# Termo3.net
KiCad netlist of a schematic drawn in EAGLE
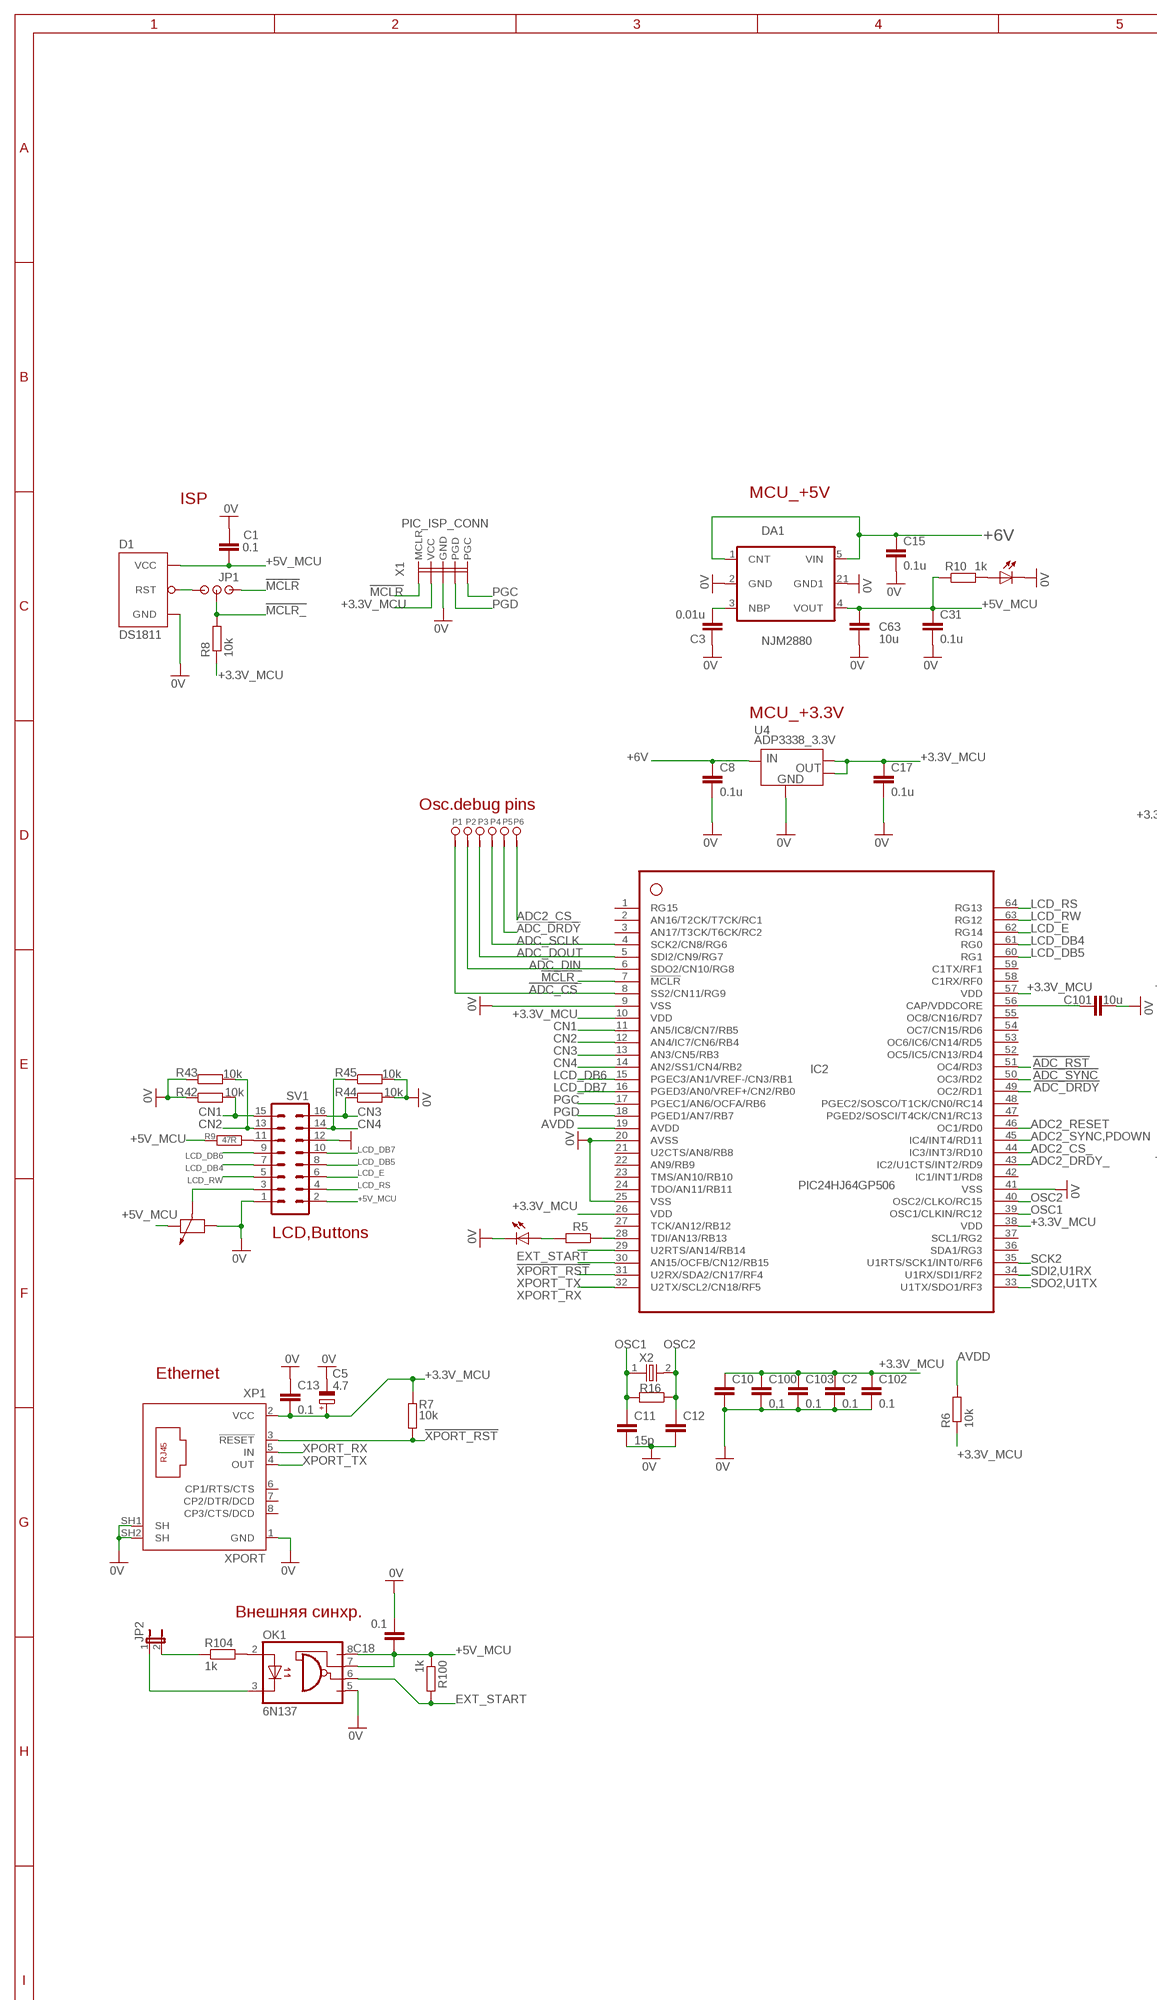
[diagram p0: schematic, sheet 1, part 1 of 2]
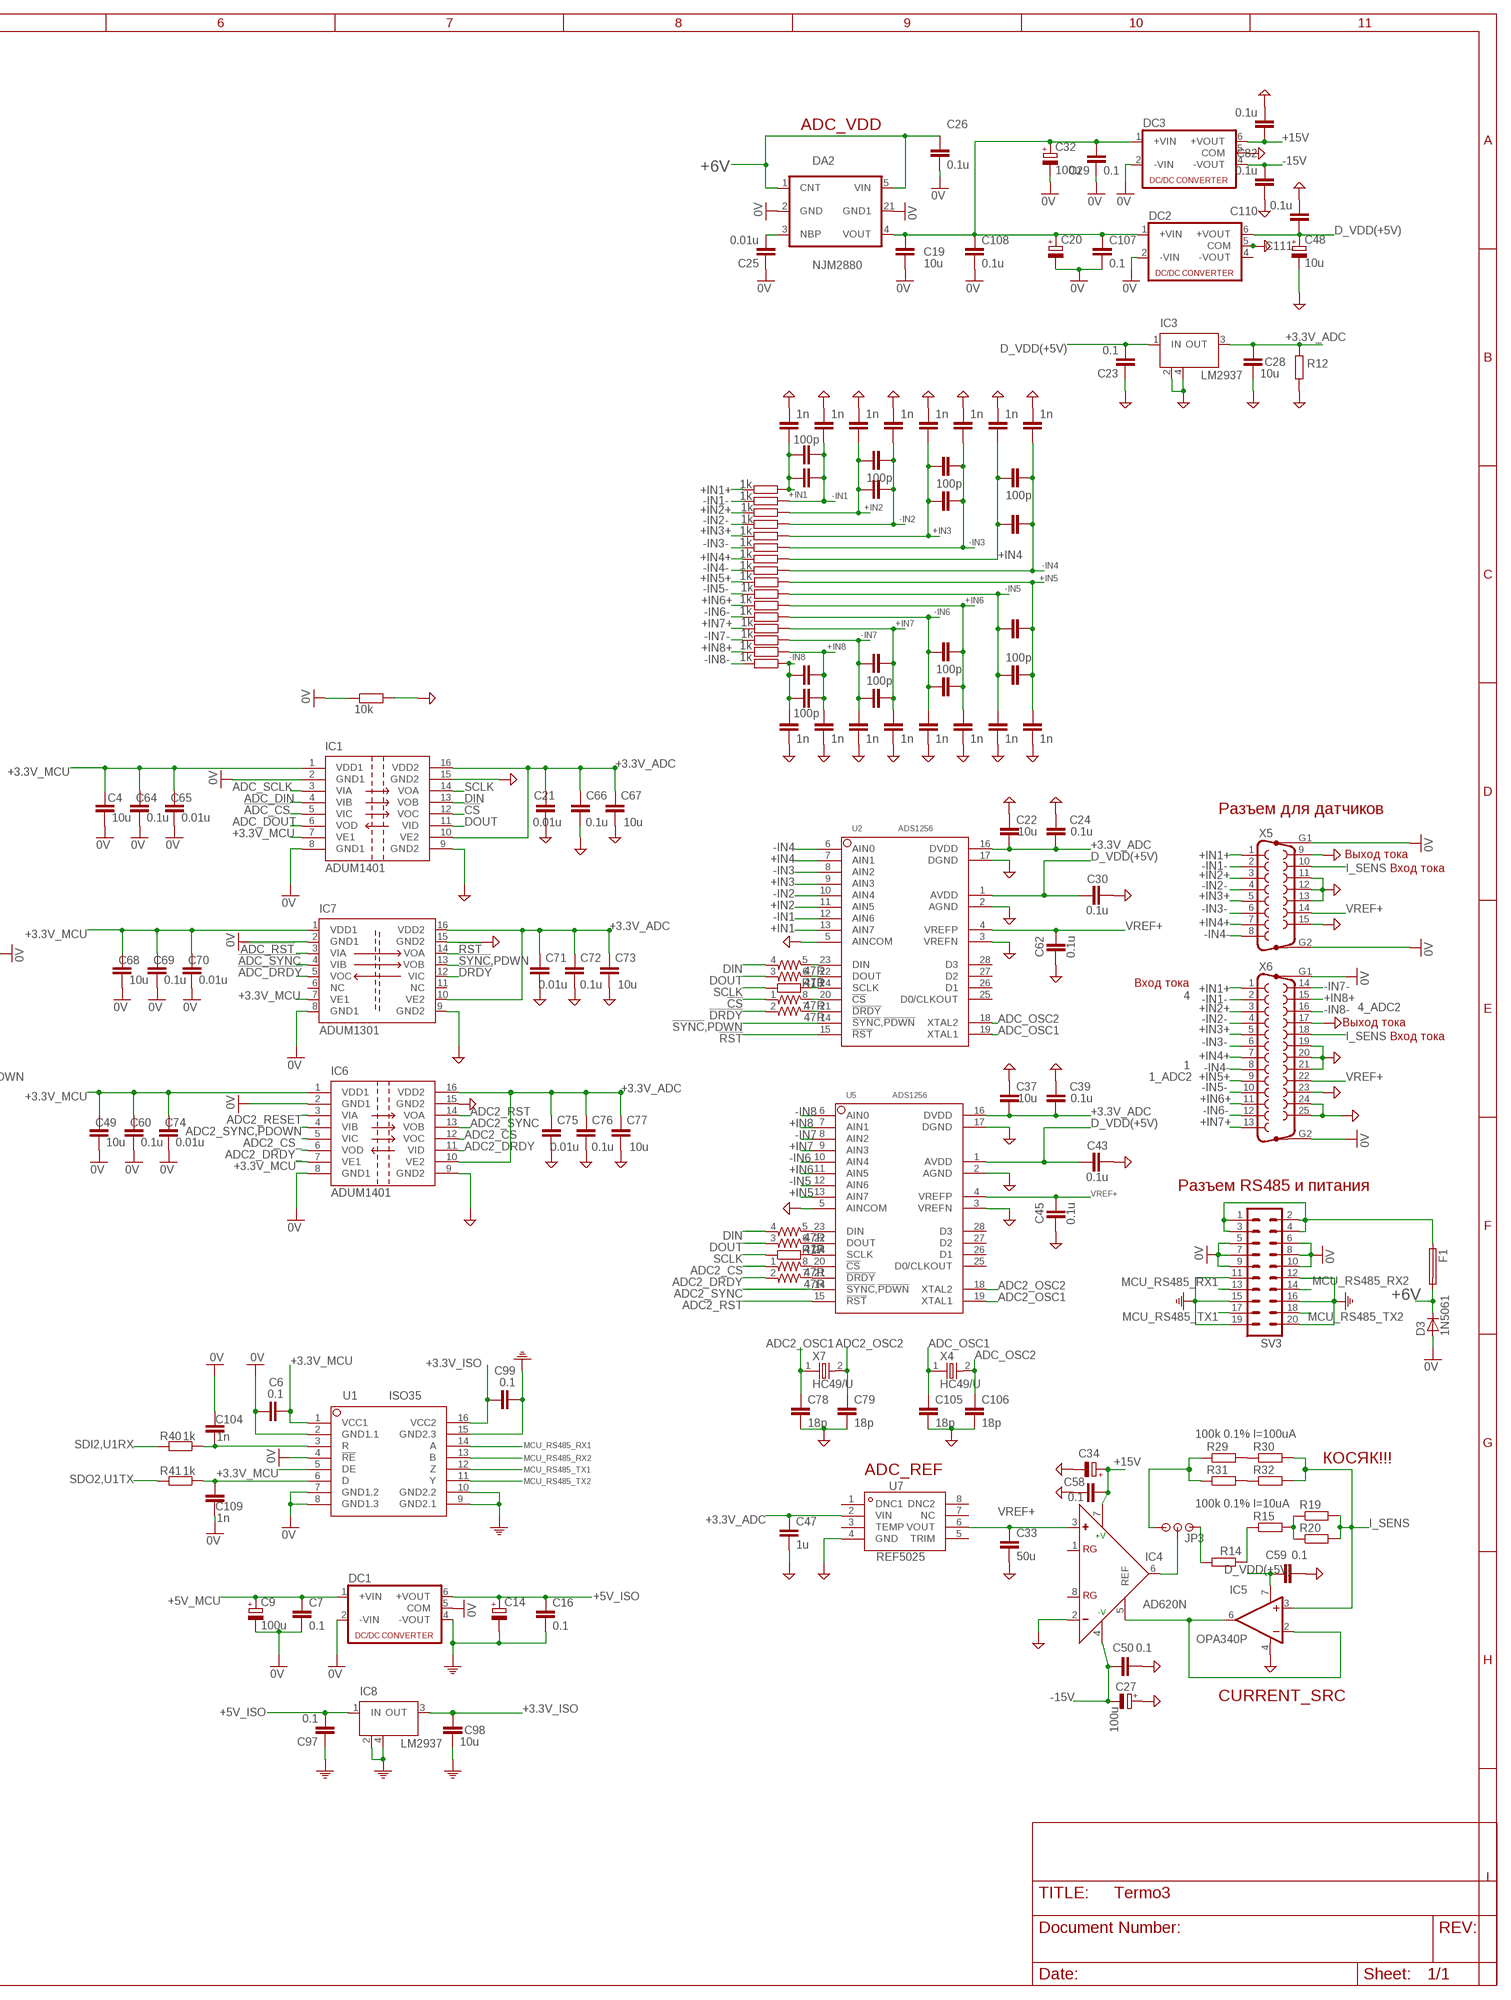
[diagram p1: schematic, sheet 1, part 2 of 2]

(export (version "E")
  (design (tool "Eeschema 10.0.6"))
  (components
    (comp (ref "C1")
      (value "0.1")
      (footprint "eagle-import:C0805D")
      (libsource (lib "eagle-import") (part "C0805"))
    )
    (comp (ref "C2")
      (value "0.1")
      (footprint "eagle-import:C0805D")
      (libsource (lib "eagle-import") (part "C0805"))
    )
    (comp (ref "C3")
      (value "0.01u")
      (footprint "eagle-import:C0805D")
      (libsource (lib "eagle-import") (part "C0805"))
    )
    (comp (ref "C4")
      (value "10u")
      (footprint "eagle-import:C0805D")
      (libsource (lib "eagle-import") (part "C0805"))
    )
    (comp (ref "C5")
      (value "4.7")
      (footprint "eagle-import:C100MILX6X12")
      (libsource (lib "eagle-import") (part "C100MFX25V"))
    )
    (comp (ref "C6")
      (value "0.1")
      (footprint "eagle-import:C0805D")
      (libsource (lib "eagle-import") (part "C0805"))
    )
    (comp (ref "C7")
      (value "0.1")
      (footprint "eagle-import:C0805D")
      (libsource (lib "eagle-import") (part "C0805"))
    )
    (comp (ref "C8")
      (value "0.1u")
      (footprint "eagle-import:C0805D")
      (libsource (lib "eagle-import") (part "C0805"))
    )
    (comp (ref "C9")
      (value "100u")
      (footprint "eagle-import:C100MILX6X12")
      (libsource (lib "eagle-import") (part "C100MFX25V"))
    )
    (comp (ref "C10")
      (value "C0805")
      (footprint "eagle-import:C0805D")
      (libsource (lib "eagle-import") (part "C0805"))
    )
    (comp (ref "C11")
      (value "15p")
      (footprint "eagle-import:C0805D")
      (libsource (lib "eagle-import") (part "C0805"))
    )
    (comp (ref "C12")
      (value "C0805")
      (footprint "eagle-import:C0805D")
      (libsource (lib "eagle-import") (part "C0805"))
    )
    (comp (ref "C13")
      (value "0.1")
      (footprint "eagle-import:C0805D")
      (libsource (lib "eagle-import") (part "C0805"))
    )
    (comp (ref "C14")
      (value "C100MFX25V")
      (footprint "eagle-import:C100MILX6X12")
      (libsource (lib "eagle-import") (part "C100MFX25V"))
    )
    (comp (ref "C15")
      (value "0.1u")
      (footprint "eagle-import:C0805D")
      (libsource (lib "eagle-import") (part "C0805"))
    )
    (comp (ref "C16")
      (value "0.1")
      (footprint "eagle-import:C0805D")
      (libsource (lib "eagle-import") (part "C0805"))
    )
    (comp (ref "C17")
      (value "0.1u")
      (footprint "eagle-import:C0805D")
      (libsource (lib "eagle-import") (part "C0805"))
    )
    (comp (ref "C18")
      (value "0.1")
      (footprint "eagle-import:C0805D")
      (libsource (lib "eagle-import") (part "C0805"))
    )
    (comp (ref "C19")
      (value "10u")
      (footprint "eagle-import:C0805D")
      (libsource (lib "eagle-import") (part "C0805"))
    )
    (comp (ref "C20")
      (value "C100MFX25V")
      (footprint "eagle-import:C100MILX6X12")
      (libsource (lib "eagle-import") (part "C100MFX25V"))
    )
    (comp (ref "C21")
      (value "0.01u")
      (footprint "eagle-import:C0805D")
      (libsource (lib "eagle-import") (part "C0805"))
    )
    (comp (ref "C22")
      (value "10u")
      (footprint "eagle-import:C0805D")
      (libsource (lib "eagle-import") (part "C0805"))
    )
    (comp (ref "C23")
      (value "0.1")
      (footprint "eagle-import:C0805D")
      (libsource (lib "eagle-import") (part "C0805"))
    )
    (comp (ref "C24")
      (value "0.1u")
      (footprint "eagle-import:C0805D")
      (libsource (lib "eagle-import") (part "C0805"))
    )
    (comp (ref "C25")
      (value "0.01u")
      (footprint "eagle-import:C0805D")
      (libsource (lib "eagle-import") (part "C0805"))
    )
    (comp (ref "C26")
      (value "0.1u")
      (footprint "eagle-import:C0805D")
      (libsource (lib "eagle-import") (part "C0805"))
    )
    (comp (ref "C27")
      (value "100u")
      (footprint "eagle-import:C100MILX6X12")
      (libsource (lib "eagle-import") (part "C100MFX25V"))
    )
    (comp (ref "C28")
      (value "10u")
      (footprint "eagle-import:C0805D")
      (libsource (lib "eagle-import") (part "C0805"))
    )
    (comp (ref "C29")
      (value "0.1")
      (footprint "eagle-import:C0805D")
      (libsource (lib "eagle-import") (part "C0805"))
    )
    (comp (ref "C30")
      (value "0.1u")
      (footprint "eagle-import:C0805D")
      (libsource (lib "eagle-import") (part "C0805"))
    )
    (comp (ref "C31")
      (value "0.1u")
      (footprint "eagle-import:C0805D")
      (libsource (lib "eagle-import") (part "C0805"))
    )
    (comp (ref "C32")
      (value "100u")
      (footprint "eagle-import:C100MILX6X12")
      (libsource (lib "eagle-import") (part "C100MFX25V"))
    )
    (comp (ref "C33")
      (value "50u")
      (footprint "eagle-import:C0805D")
      (libsource (lib "eagle-import") (part "C0805"))
    )
    (comp (ref "C34")
      (value "C100MFX25V")
      (footprint "eagle-import:C100MILX6X12")
      (libsource (lib "eagle-import") (part "C100MFX25V"))
    )
    (comp (ref "C35")
      (value "100p")
      (footprint "eagle-import:C0805D")
      (libsource (lib "eagle-import") (part "C0805"))
    )
    (comp (ref "C36")
      (value "100p")
      (footprint "eagle-import:C0805D")
      (libsource (lib "eagle-import") (part "C0805"))
    )
    (comp (ref "C37")
      (value "10u")
      (footprint "eagle-import:C0805D")
      (libsource (lib "eagle-import") (part "C0805"))
    )
    (comp (ref "C38")
      (value "100p")
      (footprint "eagle-import:C0805D")
      (libsource (lib "eagle-import") (part "C0805"))
    )
    (comp (ref "C39")
      (value "0.1u")
      (footprint "eagle-import:C0805D")
      (libsource (lib "eagle-import") (part "C0805"))
    )
    (comp (ref "C40")
      (value "100p")
      (footprint "eagle-import:C0805D")
      (libsource (lib "eagle-import") (part "C0805"))
    )
    (comp (ref "C41")
      (value "1n")
      (footprint "eagle-import:C0805D")
      (libsource (lib "eagle-import") (part "C0805"))
    )
    (comp (ref "C42")
      (value "1n")
      (footprint "eagle-import:C0805D")
      (libsource (lib "eagle-import") (part "C0805"))
    )
    (comp (ref "C43")
      (value "0.1u")
      (footprint "eagle-import:C0805D")
      (libsource (lib "eagle-import") (part "C0805"))
    )
    (comp (ref "C44")
      (value "1n")
      (footprint "eagle-import:C0805D")
      (libsource (lib "eagle-import") (part "C0805"))
    )
    (comp (ref "C45")
      (value "0.1u")
      (footprint "eagle-import:C0805D")
      (libsource (lib "eagle-import") (part "C0805"))
    )
    (comp (ref "C46")
      (value "1n")
      (footprint "eagle-import:C0805D")
      (libsource (lib "eagle-import") (part "C0805"))
    )
    (comp (ref "C47")
      (value "1u")
      (footprint "eagle-import:C0805D")
      (libsource (lib "eagle-import") (part "C0805"))
    )
    (comp (ref "C48")
      (value "10u")
      (footprint "eagle-import:C100MILX6X12")
      (libsource (lib "eagle-import") (part "C100MFX25V"))
    )
    (comp (ref "C49")
      (value "10u")
      (footprint "eagle-import:C0805D")
      (libsource (lib "eagle-import") (part "C0805"))
    )
    (comp (ref "C50")
      (value "0.1")
      (footprint "eagle-import:C0805D")
      (libsource (lib "eagle-import") (part "C0805"))
    )
    (comp (ref "C51")
      (value "1n")
      (footprint "eagle-import:C0805D")
      (libsource (lib "eagle-import") (part "C0805"))
    )
    (comp (ref "C52")
      (value "1n")
      (footprint "eagle-import:C0805D")
      (libsource (lib "eagle-import") (part "C0805"))
    )
    (comp (ref "C53")
      (value "1n")
      (footprint "eagle-import:C0805D")
      (libsource (lib "eagle-import") (part "C0805"))
    )
    (comp (ref "C54")
      (value "1n")
      (footprint "eagle-import:C0805D")
      (libsource (lib "eagle-import") (part "C0805"))
    )
    (comp (ref "C55")
      (value "1n")
      (footprint "eagle-import:C0805D")
      (libsource (lib "eagle-import") (part "C0805"))
    )
    (comp (ref "C56")
      (value "1n")
      (footprint "eagle-import:C0805D")
      (libsource (lib "eagle-import") (part "C0805"))
    )
    (comp (ref "C57")
      (value "1n")
      (footprint "eagle-import:C0805D")
      (libsource (lib "eagle-import") (part "C0805"))
    )
    (comp (ref "C58")
      (value "0.1")
      (footprint "eagle-import:C0805D")
      (libsource (lib "eagle-import") (part "C0805"))
    )
    (comp (ref "C59")
      (value "0.1")
      (footprint "eagle-import:C0805D")
      (libsource (lib "eagle-import") (part "C0805"))
    )
    (comp (ref "C60")
      (value "0.1u")
      (footprint "eagle-import:C0805D")
      (libsource (lib "eagle-import") (part "C0805"))
    )
    (comp (ref "C61")
      (value "1n")
      (footprint "eagle-import:C0805D")
      (libsource (lib "eagle-import") (part "C0805"))
    )
    (comp (ref "C62")
      (value "0.1u")
      (footprint "eagle-import:C0805D")
      (libsource (lib "eagle-import") (part "C0805"))
    )
    (comp (ref "C63")
      (value "10u")
      (footprint "eagle-import:C0805D")
      (libsource (lib "eagle-import") (part "C0805"))
    )
    (comp (ref "C64")
      (value "0.1u")
      (footprint "eagle-import:C0805D")
      (libsource (lib "eagle-import") (part "C0805"))
    )
    (comp (ref "C65")
      (value "0.01u")
      (footprint "eagle-import:C0805D")
      (libsource (lib "eagle-import") (part "C0805"))
    )
    (comp (ref "C66")
      (value "0.1u")
      (footprint "eagle-import:C0805D")
      (libsource (lib "eagle-import") (part "C0805"))
    )
    (comp (ref "C67")
      (value "10u")
      (footprint "eagle-import:C0805D")
      (libsource (lib "eagle-import") (part "C0805"))
    )
    (comp (ref "C68")
      (value "10u")
      (footprint "eagle-import:C0805D")
      (libsource (lib "eagle-import") (part "C0805"))
    )
    (comp (ref "C69")
      (value "0.1u")
      (footprint "eagle-import:C0805D")
      (libsource (lib "eagle-import") (part "C0805"))
    )
    (comp (ref "C70")
      (value "0.01u")
      (footprint "eagle-import:C0805D")
      (libsource (lib "eagle-import") (part "C0805"))
    )
    (comp (ref "C71")
      (value "0.01u")
      (footprint "eagle-import:C0805D")
      (libsource (lib "eagle-import") (part "C0805"))
    )
    (comp (ref "C72")
      (value "0.1u")
      (footprint "eagle-import:C0805D")
      (libsource (lib "eagle-import") (part "C0805"))
    )
    (comp (ref "C73")
      (value "10u")
      (footprint "eagle-import:C0805D")
      (libsource (lib "eagle-import") (part "C0805"))
    )
    (comp (ref "C74")
      (value "0.01u")
      (footprint "eagle-import:C0805D")
      (libsource (lib "eagle-import") (part "C0805"))
    )
    (comp (ref "C75")
      (value "0.01u")
      (footprint "eagle-import:C0805D")
      (libsource (lib "eagle-import") (part "C0805"))
    )
    (comp (ref "C76")
      (value "0.1u")
      (footprint "eagle-import:C0805D")
      (libsource (lib "eagle-import") (part "C0805"))
    )
    (comp (ref "C77")
      (value "10u")
      (footprint "eagle-import:C0805D")
      (libsource (lib "eagle-import") (part "C0805"))
    )
    (comp (ref "C78")
      (value "18p")
      (footprint "eagle-import:C0805D")
      (libsource (lib "eagle-import") (part "C0805"))
    )
    (comp (ref "C79")
      (value "18p")
      (footprint "eagle-import:C0805D")
      (libsource (lib "eagle-import") (part "C0805"))
    )
    (comp (ref "C80")
      (value "1n")
      (footprint "eagle-import:C0805D")
      (libsource (lib "eagle-import") (part "C0805"))
    )
    (comp (ref "C81")
      (value "1n")
      (footprint "eagle-import:C0805D")
      (libsource (lib "eagle-import") (part "C0805"))
    )
    (comp (ref "C82")
      (value "0.1u")
      (footprint "eagle-import:C0805D")
      (libsource (lib "eagle-import") (part "C0805"))
    )
    (comp (ref "C83")
      (value "1n")
      (footprint "eagle-import:C0805D")
      (libsource (lib "eagle-import") (part "C0805"))
    )
    (comp (ref "C84")
      (value "1n")
      (footprint "eagle-import:C0805D")
      (libsource (lib "eagle-import") (part "C0805"))
    )
    (comp (ref "C85")
      (value "1n")
      (footprint "eagle-import:C0805D")
      (libsource (lib "eagle-import") (part "C0805"))
    )
    (comp (ref "C86")
      (value "1n")
      (footprint "eagle-import:C0805D")
      (libsource (lib "eagle-import") (part "C0805"))
    )
    (comp (ref "C87")
      (value "1n")
      (footprint "eagle-import:C0805D")
      (libsource (lib "eagle-import") (part "C0805"))
    )
    (comp (ref "C88")
      (value "1n")
      (footprint "eagle-import:C0805D")
      (libsource (lib "eagle-import") (part "C0805"))
    )
    (comp (ref "C89")
      (value "1n")
      (footprint "eagle-import:C0805D")
      (libsource (lib "eagle-import") (part "C0805"))
    )
    (comp (ref "C90")
      (value "100p")
      (footprint "eagle-import:C0805D")
      (libsource (lib "eagle-import") (part "C0805"))
    )
    (comp (ref "C91")
      (value "1n")
      (footprint "eagle-import:C0805D")
      (libsource (lib "eagle-import") (part "C0805"))
    )
    (comp (ref "C92")
      (value "1n")
      (footprint "eagle-import:C0805D")
      (libsource (lib "eagle-import") (part "C0805"))
    )
    (comp (ref "C93")
      (value "1n")
      (footprint "eagle-import:C0805D")
      (libsource (lib "eagle-import") (part "C0805"))
    )
    (comp (ref "C94")
      (value "100p")
      (footprint "eagle-import:C0805D")
      (libsource (lib "eagle-import") (part "C0805"))
    )
    (comp (ref "C95")
      (value "100p")
      (footprint "eagle-import:C0805D")
      (libsource (lib "eagle-import") (part "C0805"))
    )
    (comp (ref "C96")
      (value "100p")
      (footprint "eagle-import:C0805D")
      (libsource (lib "eagle-import") (part "C0805"))
    )
    (comp (ref "C97")
      (value "0.1")
      (footprint "eagle-import:C0805D")
      (libsource (lib "eagle-import") (part "C0805"))
    )
    (comp (ref "C98")
      (value "10u")
      (footprint "eagle-import:C0805D")
      (libsource (lib "eagle-import") (part "C0805"))
    )
    (comp (ref "C99")
      (value "0.1")
      (footprint "eagle-import:C0805D")
      (libsource (lib "eagle-import") (part "C0805"))
    )
    (comp (ref "C100")
      (value "0,1")
      (footprint "eagle-import:C0805D")
      (libsource (lib "eagle-import") (part "C0805"))
    )
    (comp (ref "C101")
      (value "10u")
      (footprint "eagle-import:C0805D")
      (libsource (lib "eagle-import") (part "C0805"))
    )
    (comp (ref "C102")
      (value "0.1")
      (footprint "eagle-import:C0805D")
      (libsource (lib "eagle-import") (part "C0805"))
    )
    (comp (ref "C103")
      (value "0.1")
      (footprint "eagle-import:C0805D")
      (libsource (lib "eagle-import") (part "C0805"))
    )
    (comp (ref "C104")
      (value "1n")
      (footprint "eagle-import:C0805D")
      (libsource (lib "eagle-import") (part "C0805"))
    )
    (comp (ref "C105")
      (value "18p")
      (footprint "eagle-import:C0805D")
      (libsource (lib "eagle-import") (part "C0805"))
    )
    (comp (ref "C106")
      (value "18p")
      (footprint "eagle-import:C0805D")
      (libsource (lib "eagle-import") (part "C0805"))
    )
    (comp (ref "C107")
      (value "0.1")
      (footprint "eagle-import:C0805D")
      (libsource (lib "eagle-import") (part "C0805"))
    )
    (comp (ref "C108")
      (value "0.1u")
      (footprint "eagle-import:C0805D")
      (libsource (lib "eagle-import") (part "C0805"))
    )
    (comp (ref "C109")
      (value "1n")
      (footprint "eagle-import:C0805D")
      (libsource (lib "eagle-import") (part "C0805"))
    )
    (comp (ref "C110")
      (value "0.1u")
      (footprint "eagle-import:C0805D")
      (libsource (lib "eagle-import") (part "C0805"))
    )
    (comp (ref "C111")
      (value "0.1u")
      (footprint "eagle-import:C0805D")
      (libsource (lib "eagle-import") (part "C0805"))
    )
    (comp (ref "D1")
      (value "DS1811")
      (footprint "eagle-import:TO92-60")
      (libsource (lib "eagle-import") (part "DS1811"))
    )
    (comp (ref "D3")
      (value "1N5061")
      (footprint "eagle-import:DO41-10")
      (libsource (lib "eagle-import") (part "1N5061"))
    )
    (comp (ref "DA1")
      (value "NJM2880")
      (footprint "eagle-import:SOT89-5")
      (libsource (lib "eagle-import") (part "NJM2880"))
    )
    (comp (ref "DA2")
      (value "NJM2880")
      (footprint "eagle-import:SOT89-5")
      (libsource (lib "eagle-import") (part "NJM2880"))
    )
    (comp (ref "DC1")
      (value "NMA")
      (footprint "eagle-import:NMA")
      (fields (field (name "MF") "C & D TECHNOLOGIES, INC") (field (name "MPN") "NMA0515SC"))
      (libsource (lib "eagle-import") (part "NMA"))
    )
    (comp (ref "DC2")
      (value "NMA")
      (footprint "eagle-import:NMA")
      (fields (field (name "MF") "C & D TECHNOLOGIES, INC") (field (name "MPN") "NMA0515SC"))
      (libsource (lib "eagle-import") (part "NMA"))
    )
    (comp (ref "DC3")
      (value "NMA")
      (footprint "eagle-import:NMA")
      (fields (field (name "MF") "C & D TECHNOLOGIES, INC") (field (name "MPN") "NMA0515SC"))
      (libsource (lib "eagle-import") (part "NMA"))
    )
    (comp (ref "F1")
      (value "TE5")
      (footprint "eagle-import:TE5")
      (libsource (lib "eagle-import") (part "TE5"))
    )
    (comp (ref "HL2")
      (value "LED3MM")
      (footprint "eagle-import:LED3MM")
      (libsource (lib "eagle-import") (part "LED3MM"))
    )
    (comp (ref "HL6")
      (value "LED3MM")
      (footprint "eagle-import:LED3MM")
      (libsource (lib "eagle-import") (part "LED3MM"))
    )
    (comp (ref "IC1")
      (value "ADUM1401")
      (footprint "eagle-import:SO16W")
      (libsource (lib "eagle-import") (part "ADUM1401"))
    )
    (comp (ref "IC2")
      (value "PIC24HJ64GP506")
      (footprint "eagle-import:TQFP64-10X10")
      (fields (field (name "MPN") "PIC24HJ64GP506A-I/PT"))
      (libsource (lib "eagle-import") (part "PIC24HJ64GP506"))
    )
    (comp (ref "IC3")
      (value "LM2937")
      (footprint "eagle-import:SOT223")
      (libsource (lib "eagle-import") (part "LM2937"))
    )
    (comp (ref "IC4")
      (value "AD620N")
      (footprint "eagle-import:DIL08")
      (fields (field (name "MF") "ALTERA CORPORATION") (field (name "MPN") "AD620AN"))
      (libsource (lib "eagle-import") (part "AD620N"))
    )
    (comp (ref "IC5")
      (value "OPA340P")
      (footprint "eagle-import:DIL08")
      (fields (field (name "MPN") "OPA340PA"))
      (libsource (lib "eagle-import") (part "OPA340P"))
    )
    (comp (ref "IC6")
      (value "ADUM1401")
      (footprint "eagle-import:SO16W")
      (libsource (lib "eagle-import") (part "ADUM1401"))
    )
    (comp (ref "IC7")
      (value "ADUM1301")
      (footprint "eagle-import:SO-16W")
      (fields (field (name "MPN") "ADUM1301BRWZ"))
      (libsource (lib "eagle-import") (part "ADUM1301"))
    )
    (comp (ref "IC8")
      (value "LM2937")
      (footprint "eagle-import:SOT223")
      (libsource (lib "eagle-import") (part "LM2937"))
    )
    (comp (ref "JP1")
      (value "JP3PIN")
      (footprint "eagle-import:PLC-3PIN")
      (libsource (lib "eagle-import") (part "JP3PIN"))
    )
    (comp (ref "JP2")
      (value "JP1E")
      (footprint "eagle-import:JP1")
      (libsource (lib "eagle-import") (part "JP1E"))
    )
    (comp (ref "JP3")
      (value "JP3PIN")
      (footprint "eagle-import:PLC-3PIN")
      (libsource (lib "eagle-import") (part "JP3PIN"))
    )
    (comp (ref "OK1")
      (value "6N137")
      (footprint "eagle-import:DIL08")
      (libsource (lib "eagle-import") (part "6N137"))
    )
    (comp (ref "P1")
      (value "1_PIN_CON")
      (footprint "eagle-import:1_PIN_CON")
      (libsource (lib "eagle-import") (part "1_PIN_CON"))
    )
    (comp (ref "P2")
      (value "1_PIN_CON")
      (footprint "eagle-import:1_PIN_CON")
      (libsource (lib "eagle-import") (part "1_PIN_CON"))
    )
    (comp (ref "P3")
      (value "1_PIN_CON")
      (footprint "eagle-import:1_PIN_CON")
      (libsource (lib "eagle-import") (part "1_PIN_CON"))
    )
    (comp (ref "P4")
      (value "1_PIN_CON")
      (footprint "eagle-import:1_PIN_CON")
      (libsource (lib "eagle-import") (part "1_PIN_CON"))
    )
    (comp (ref "P5")
      (value "1_PIN_CON")
      (footprint "eagle-import:1_PIN_CON")
      (libsource (lib "eagle-import") (part "1_PIN_CON"))
    )
    (comp (ref "P6")
      (value "1_PIN_CON")
      (footprint "eagle-import:1_PIN_CON")
      (libsource (lib "eagle-import") (part "1_PIN_CON"))
    )
    (comp (ref "POT1")
      (value "RTRIM3329H")
      (footprint "eagle-import:RTRIM3329H")
      (libsource (lib "eagle-import") (part "RTRIM3329H"))
    )
    (comp (ref "R5")
      (value "51R")
      (footprint "eagle-import:R0805D")
      (libsource (lib "eagle-import") (part "R0805"))
    )
    (comp (ref "R6")
      (value "10k")
      (footprint "eagle-import:R0805D")
      (libsource (lib "eagle-import") (part "R0805"))
    )
    (comp (ref "R7")
      (value "10k")
      (footprint "eagle-import:R0805D")
      (libsource (lib "eagle-import") (part "R0805"))
    )
    (comp (ref "R8")
      (value "10k")
      (footprint "eagle-import:R0805D")
      (libsource (lib "eagle-import") (part "R0805"))
    )
    (comp (ref "R9")
      (value "47R")
      (footprint "eagle-import:0207_10")
      (libsource (lib "eagle-import") (part "MLT025{dblquote}"))
    )
    (comp (ref "R10")
      (value "1k")
      (footprint "eagle-import:R0805D")
      (libsource (lib "eagle-import") (part "R0805"))
    )
    (comp (ref "R11")
      (value "10k")
      (footprint "eagle-import:R0805D")
      (libsource (lib "eagle-import") (part "R0805"))
    )
    (comp (ref "R12")
      (value "1k")
      (footprint "eagle-import:R0805D")
      (libsource (lib "eagle-import") (part "R0805"))
    )
    (comp (ref "R13")
      (value "51R")
      (footprint "eagle-import:R0805D")
      (libsource (lib "eagle-import") (part "R0805"))
    )
    (comp (ref "R14")
      (value "MLT025\"")
      (footprint "eagle-import:0207_10")
      (libsource (lib "eagle-import") (part "MLT025{dblquote}"))
    )
    (comp (ref "R15")
      (value "100k 0.1% I=10uA")
      (footprint "eagle-import:0207_10")
      (libsource (lib "eagle-import") (part "MLT025{dblquote}"))
    )
    (comp (ref "R16")
      (value "1M")
      (footprint "eagle-import:R0805D")
      (libsource (lib "eagle-import") (part "R0805"))
    )
    (comp (ref "R17")
      (value "51R")
      (footprint "eagle-import:R0805D")
      (libsource (lib "eagle-import") (part "R0805"))
    )
    (comp (ref "R18")
      (value "1k")
      (footprint "eagle-import:R0805D")
      (libsource (lib "eagle-import") (part "R0805"))
    )
    (comp (ref "R19")
      (value "MLT025\"")
      (footprint "eagle-import:0207_10")
      (libsource (lib "eagle-import") (part "MLT025{dblquote}"))
    )
    (comp (ref "R20")
      (value "MLT025\"")
      (footprint "eagle-import:0207_10")
      (libsource (lib "eagle-import") (part "MLT025{dblquote}"))
    )
    (comp (ref "R21")
      (value "1k")
      (footprint "eagle-import:R0805D")
      (libsource (lib "eagle-import") (part "R0805"))
    )
    (comp (ref "R22")
      (value "1k")
      (footprint "eagle-import:R0805D")
      (libsource (lib "eagle-import") (part "R0805"))
    )
    (comp (ref "R23")
      (value "1k")
      (footprint "eagle-import:R0805D")
      (libsource (lib "eagle-import") (part "R0805"))
    )
    (comp (ref "R24")
      (value "1k")
      (footprint "eagle-import:R0805D")
      (libsource (lib "eagle-import") (part "R0805"))
    )
    (comp (ref "R25")
      (value "1k")
      (footprint "eagle-import:R0805D")
      (libsource (lib "eagle-import") (part "R0805"))
    )
    (comp (ref "R26")
      (value "1k")
      (footprint "eagle-import:R0805D")
      (libsource (lib "eagle-import") (part "R0805"))
    )
    (comp (ref "R27")
      (value "1k")
      (footprint "eagle-import:R0805D")
      (libsource (lib "eagle-import") (part "R0805"))
    )
    (comp (ref "R28")
      (value "1k")
      (footprint "eagle-import:R0805D")
      (libsource (lib "eagle-import") (part "R0805"))
    )
    (comp (ref "R29")
      (value "100k 0.1% I=100uA")
      (footprint "eagle-import:0207_10")
      (libsource (lib "eagle-import") (part "MLT025{dblquote}"))
    )
    (comp (ref "R30")
      (value "MLT025\"")
      (footprint "eagle-import:0207_10")
      (libsource (lib "eagle-import") (part "MLT025{dblquote}"))
    )
    (comp (ref "R31")
      (value "MLT025\"")
      (footprint "eagle-import:0207_10")
      (libsource (lib "eagle-import") (part "MLT025{dblquote}"))
    )
    (comp (ref "R32")
      (value "MLT025\"")
      (footprint "eagle-import:0207_10")
      (libsource (lib "eagle-import") (part "MLT025{dblquote}"))
    )
    (comp (ref "R33")
      (value "1k")
      (footprint "eagle-import:R0805D")
      (libsource (lib "eagle-import") (part "R0805"))
    )
    (comp (ref "R34")
      (value "1k")
      (footprint "eagle-import:R0805D")
      (libsource (lib "eagle-import") (part "R0805"))
    )
    (comp (ref "R35")
      (value "1k")
      (footprint "eagle-import:R0805D")
      (libsource (lib "eagle-import") (part "R0805"))
    )
    (comp (ref "R36")
      (value "1k")
      (footprint "eagle-import:R0805D")
      (libsource (lib "eagle-import") (part "R0805"))
    )
    (comp (ref "R37")
      (value "1k")
      (footprint "eagle-import:R0805D")
      (libsource (lib "eagle-import") (part "R0805"))
    )
    (comp (ref "R38")
      (value "1k")
      (footprint "eagle-import:R0805D")
      (libsource (lib "eagle-import") (part "R0805"))
    )
    (comp (ref "R39")
      (value "1k")
      (footprint "eagle-import:R0805D")
      (libsource (lib "eagle-import") (part "R0805"))
    )
    (comp (ref "R40")
      (value "1k")
      (footprint "eagle-import:R0805D")
      (libsource (lib "eagle-import") (part "R0805"))
    )
    (comp (ref "R41")
      (value "1k")
      (footprint "eagle-import:R0805D")
      (libsource (lib "eagle-import") (part "R0805"))
    )
    (comp (ref "R42")
      (value "10k")
      (footprint "eagle-import:R0805D")
      (libsource (lib "eagle-import") (part "R0805"))
    )
    (comp (ref "R43")
      (value "10k")
      (footprint "eagle-import:R0805D")
      (libsource (lib "eagle-import") (part "R0805"))
    )
    (comp (ref "R44")
      (value "10k")
      (footprint "eagle-import:R0805D")
      (libsource (lib "eagle-import") (part "R0805"))
    )
    (comp (ref "R45")
      (value "10k")
      (footprint "eagle-import:R0805D")
      (libsource (lib "eagle-import") (part "R0805"))
    )
    (comp (ref "R100")
      (value "1k")
      (footprint "eagle-import:R0805D")
      (libsource (lib "eagle-import") (part "R0805"))
    )
    (comp (ref "R104")
      (value "1k")
      (footprint "eagle-import:R0805D")
      (libsource (lib "eagle-import") (part "R0805"))
    )
    (comp (ref "RN1")
      (value "47R")
      (footprint "eagle-import:742-8NS")
      (libsource (lib "eagle-import") (part "742-8_SNS"))
    )
    (comp (ref "RN2")
      (value "47R")
      (footprint "eagle-import:742-8NS")
      (libsource (lib "eagle-import") (part "742-8_SNS"))
    )
    (comp (ref "SV1")
      (value "ML16")
      (footprint "eagle-import:ML16")
      (fields (field (name "OC_FARNELL") "unknown") (field (name "OC_NEWARK") "unknown"))
      (libsource (lib "eagle-import") (part "ML16"))
    )
    (comp (ref "SV3")
      (value "ML20L")
      (footprint "eagle-import:ML20L")
      (libsource (lib "eagle-import") (part "ML20L"))
    )
    (comp (ref "U1")
      (value "ISO35")
      (footprint "eagle-import:ISO35_SOIC16")
      (libsource (lib "eagle-import") (part "ISO35"))
    )
    (comp (ref "U2")
      (value "ADS1256")
      (footprint "eagle-import:PCM2705-TSSOP28")
      (libsource (lib "eagle-import") (part "ADS1256"))
    )
    (comp (ref "U4")
      (value "ADP3338_3.3V")
      (footprint "eagle-import:SOT223")
      (libsource (lib "eagle-import") (part "ADP3338_3.3V"))
    )
    (comp (ref "U5")
      (value "ADS1256")
      (footprint "eagle-import:PCM2705-TSSOP28")
      (libsource (lib "eagle-import") (part "ADS1256"))
    )
    (comp (ref "U7")
      (value "REF5025")
      (footprint "eagle-import:SO08")
      (libsource (lib "eagle-import") (part "REF5025"))
    )
    (comp (ref "X1")
      (value "PIC_ISP_CONN")
      (footprint "eagle-import:PLC-5PIN")
      (libsource (lib "eagle-import") (part "PIC_ISP_CONN"))
    )
    (comp (ref "X2")
      (value "10MEG")
      (footprint "eagle-import:HC49U-V")
      (libsource (lib "eagle-import") (part "HC49/U"))
    )
    (comp (ref "X4")
      (value "HC49/U")
      (footprint "eagle-import:HC49U-V")
      (libsource (lib "eagle-import") (part "HC49/U"))
    )
    (comp (ref "X5")
      (value "F15HP")
      (footprint "eagle-import:F15HP")
      (libsource (lib "eagle-import") (part "F15HP"))
    )
    (comp (ref "X6")
      (value "F25HP")
      (footprint "eagle-import:F25HP")
      (libsource (lib "eagle-import") (part "F25HP"))
    )
    (comp (ref "X7")
      (value "HC49/U")
      (footprint "eagle-import:HC49U-V")
      (libsource (lib "eagle-import") (part "HC49/U"))
    )
    (comp (ref "XP1")
      (value "XPORT")
      (footprint "eagle-import:XPORT")
      (libsource (lib "eagle-import") (part "XPORT"))
    )
  )
  (nets
    (net (code "1") (name "/+3.3V_ADC") (class "Default")
      (node (ref "C21") (pin "2") (pinfunction "2_2") (pintype "passive"))
      (node (ref "C22") (pin "2") (pinfunction "2_2") (pintype "passive"))
      (node (ref "C24") (pin "1") (pinfunction "1_1") (pintype "passive"))
      (node (ref "C28") (pin "2") (pinfunction "2_2") (pintype "passive"))
      (node (ref "C37") (pin "2") (pinfunction "2_2") (pintype "passive"))
      (node (ref "C39") (pin "1") (pinfunction "1_1") (pintype "passive"))
      (node (ref "C47") (pin "1") (pinfunction "1_1") (pintype "passive"))
      (node (ref "C66") (pin "2") (pinfunction "2_2") (pintype "passive"))
      (node (ref "C67") (pin "2") (pinfunction "2_2") (pintype "passive"))
      (node (ref "C71") (pin "2") (pinfunction "2_2") (pintype "passive"))
      (node (ref "C72") (pin "2") (pinfunction "2_2") (pintype "passive"))
      (node (ref "C73") (pin "2") (pinfunction "2_2") (pintype "passive"))
      (node (ref "C75") (pin "2") (pinfunction "2_2") (pintype "passive"))
      (node (ref "C76") (pin "2") (pinfunction "2_2") (pintype "passive"))
      (node (ref "C77") (pin "2") (pinfunction "2_2") (pintype "passive"))
      (node (ref "IC1") (pin "10") (pinfunction "VE2_10") (pintype "passive"))
      (node (ref "IC1") (pin "16") (pinfunction "VDD2_16") (pintype "power_in"))
      (node (ref "IC3") (pin "3") (pinfunction "OUT_3") (pintype "passive"))
      (node (ref "IC6") (pin "10") (pinfunction "VE2_10") (pintype "passive"))
      (node (ref "IC6") (pin "16") (pinfunction "VDD2_16") (pintype "power_in"))
      (node (ref "IC7") (pin "10") (pinfunction "VE2_10") (pintype "input"))
      (node (ref "IC7") (pin "16") (pinfunction "VDD2_16") (pintype "input"))
      (node (ref "R12") (pin "P$2") (pinfunction "2_P$2") (pintype "passive"))
      (node (ref "U2") (pin "16") (pinfunction "DVDD_16") (pintype "bidirectional"))
      (node (ref "U5") (pin "16") (pinfunction "DVDD_16") (pintype "bidirectional"))
      (node (ref "U7") (pin "2") (pinfunction "VIN_2") (pintype "bidirectional"))
    )
    (net (code "2") (name "/+3.3V_ISO") (class "Default")
      (node (ref "C98") (pin "2") (pinfunction "2_2") (pintype "passive"))
      (node (ref "C99") (pin "1") (pinfunction "1_1") (pintype "passive"))
      (node (ref "IC8") (pin "3") (pinfunction "OUT_3") (pintype "passive"))
      (node (ref "U1") (pin "16") (pinfunction "VCC2_16") (pintype "bidirectional"))
    )
    (net (code "3") (name "/+3.3V_MCU") (class "Default")
      (node (ref "C10") (pin "1") (pinfunction "1_1") (pintype "passive"))
      (node (ref "C100") (pin "1") (pinfunction "1_1") (pintype "passive"))
      (node (ref "C102") (pin "1") (pinfunction "1_1") (pintype "passive"))
      (node (ref "C103") (pin "1") (pinfunction "1_1") (pintype "passive"))
      (node (ref "C13") (pin "2") (pinfunction "2_2") (pintype "passive"))
      (node (ref "C17") (pin "1") (pinfunction "1_1") (pintype "passive"))
      (node (ref "C2") (pin "1") (pinfunction "1_1") (pintype "passive"))
      (node (ref "C4") (pin "1") (pinfunction "1_1") (pintype "passive"))
      (node (ref "C49") (pin "1") (pinfunction "1_1") (pintype "passive"))
      (node (ref "C5") (pin "PLUS") (pinfunction "+_PLUS") (pintype "passive"))
      (node (ref "C6") (pin "2") (pinfunction "2_2") (pintype "passive"))
      (node (ref "C60") (pin "1") (pinfunction "1_1") (pintype "passive"))
      (node (ref "C64") (pin "1") (pinfunction "1_1") (pintype "passive"))
      (node (ref "C65") (pin "1") (pinfunction "1_1") (pintype "passive"))
      (node (ref "C68") (pin "1") (pinfunction "1_1") (pintype "passive"))
      (node (ref "C69") (pin "1") (pinfunction "1_1") (pintype "passive"))
      (node (ref "C70") (pin "1") (pinfunction "1_1") (pintype "passive"))
      (node (ref "C74") (pin "1") (pinfunction "1_1") (pintype "passive"))
      (node (ref "IC1") (pin "1") (pinfunction "VDD1_1") (pintype "power_in"))
      (node (ref "IC1") (pin "7") (pinfunction "VE1_7") (pintype "passive"))
      (node (ref "IC2") (pin "10") (pinfunction "VDD_10") (pintype "power_in"))
      (node (ref "IC2") (pin "26") (pinfunction "VDD_26") (pintype "power_in"))
      (node (ref "IC2") (pin "38") (pinfunction "VDD_38") (pintype "power_in"))
      (node (ref "IC2") (pin "57") (pinfunction "VDD_57") (pintype "power_in"))
      (node (ref "IC6") (pin "1") (pinfunction "VDD1_1") (pintype "power_in"))
      (node (ref "IC6") (pin "7") (pinfunction "VE1_7") (pintype "passive"))
      (node (ref "IC7") (pin "1") (pinfunction "VDD1_1") (pintype "input"))
      (node (ref "IC7") (pin "7") (pinfunction "VE1_7") (pintype "input"))
      (node (ref "R6") (pin "P$1") (pinfunction "1_P$1") (pintype "passive"))
      (node (ref "R7") (pin "P$1") (pinfunction "1_P$1") (pintype "passive"))
      (node (ref "R8") (pin "P$1") (pinfunction "1_P$1") (pintype "passive"))
      (node (ref "U1") (pin "1") (pinfunction "VCC1_1") (pintype "bidirectional"))
      (node (ref "U1") (pin "5") (pinfunction "DE_5") (pintype "bidirectional"))
      (node (ref "U4") (pin "2") (pinfunction "2_2") (pintype "bidirectional"))
      (node (ref "U4") (pin "4") (pinfunction "2._4") (pintype "bidirectional"))
      (node (ref "X1") (pin "P$2") (pinfunction "VCC_P$2") (pintype "bidirectional"))
      (node (ref "XP1") (pin "2") (pinfunction "VCC_2") (pintype "power_in"))
    )
    (net (code "4") (name "/+5V_ISO") (class "Default")
      (node (ref "C14") (pin "PLUS") (pinfunction "+_PLUS") (pintype "passive"))
      (node (ref "C16") (pin "1") (pinfunction "1_1") (pintype "passive"))
      (node (ref "C97") (pin "2") (pinfunction "2_2") (pintype "passive"))
      (node (ref "DC1") (pin "6") (pinfunction "+VOUT_6") (pintype "passive"))
      (node (ref "IC8") (pin "1") (pinfunction "IN_1") (pintype "input"))
    )
    (net (code "5") (name "/+5V_MCU") (class "Default")
      (node (ref "C1") (pin "1") (pinfunction "1_1") (pintype "passive"))
      (node (ref "C18") (pin "1") (pinfunction "1_1") (pintype "passive"))
      (node (ref "C31") (pin "1") (pinfunction "1_1") (pintype "passive"))
      (node (ref "C63") (pin "2") (pinfunction "2_2") (pintype "passive"))
      (node (ref "C7") (pin "1") (pinfunction "1_1") (pintype "passive"))
      (node (ref "C9") (pin "PLUS") (pinfunction "+_PLUS") (pintype "passive"))
      (node (ref "D1") (pin "2") (pinfunction "VCC_2") (pintype "power_in"))
      (node (ref "DA1") (pin "4") (pinfunction "VOUT_4") (pintype "bidirectional"))
      (node (ref "DC1") (pin "1") (pinfunction "+VIN_1") (pintype "passive"))
      (node (ref "OK1") (pin "7") (pinfunction "VE_7") (pintype "passive"))
      (node (ref "OK1") (pin "8") (pinfunction "VCC_8") (pintype "passive"))
      (node (ref "POT1") (pin "2") (pinfunction "2_2") (pintype "passive"))
      (node (ref "R10") (pin "P$1") (pinfunction "1_P$1") (pintype "passive"))
      (node (ref "R100") (pin "P$1") (pinfunction "1_P$1") (pintype "passive"))
      (node (ref "R9") (pin "2") (pinfunction "2_2") (pintype "passive"))
      (node (ref "SV1") (pin "2") (pinfunction "2_2") (pintype "passive"))
    )
    (net (code "6") (name "/+6V") (class "Default")
      (node (ref "C15") (pin "1") (pinfunction "1_1") (pintype "passive"))
      (node (ref "C26") (pin "1") (pinfunction "1_1") (pintype "passive"))
      (node (ref "C8") (pin "1") (pinfunction "1_1") (pintype "passive"))
      (node (ref "D3") (pin "C") (pinfunction "C_C") (pintype "passive"))
      (node (ref "DA1") (pin "1") (pinfunction "CNT_1") (pintype "bidirectional"))
      (node (ref "DA1") (pin "5") (pinfunction "VIN_5") (pintype "bidirectional"))
      (node (ref "DA2") (pin "1") (pinfunction "CNT_1") (pintype "bidirectional"))
      (node (ref "DA2") (pin "5") (pinfunction "VIN_5") (pintype "bidirectional"))
      (node (ref "F1") (pin "2") (pinfunction "2_2") (pintype "passive"))
      (node (ref "U4") (pin "3") (pinfunction "3_3") (pintype "bidirectional"))
    )
    (net (code "7") (name "/+15V") (class "Default")
      (node (ref "C34") (pin "PLUS") (pinfunction "+_PLUS") (pintype "passive"))
      (node (ref "C58") (pin "2") (pinfunction "2_2") (pintype "passive"))
      (node (ref "C82") (pin "1") (pinfunction "1_1") (pintype "passive"))
      (node (ref "DC3") (pin "6") (pinfunction "+VOUT_6") (pintype "passive"))
      (node (ref "IC4") (pin "7") (pinfunction "+V_7") (pintype "power_in"))
    )
    (net (code "8") (name "/+IN1") (class "Default")
      (node (ref "C35") (pin "1") (pinfunction "1_1") (pintype "passive"))
      (node (ref "C41") (pin "1") (pinfunction "1_1") (pintype "passive"))
      (node (ref "C51") (pin "1") (pinfunction "1_1") (pintype "passive"))
      (node (ref "R22") (pin "P$1") (pinfunction "1_P$1") (pintype "passive"))
      (node (ref "U2") (pin "13") (pinfunction "AIN7_13") (pintype "bidirectional"))
    )
    (net (code "9") (name "/+IN1+") (class "Default")
      (node (ref "R22") (pin "P$2") (pinfunction "2_P$2") (pintype "passive"))
      (node (ref "X5") (pin "1") (pinfunction "1_1") (pintype "passive"))
      (node (ref "X6") (pin "1") (pinfunction "1_1") (pintype "passive"))
    )
    (net (code "10") (name "/+IN2") (class "Default")
      (node (ref "C40") (pin "1") (pinfunction "1_1") (pintype "passive"))
      (node (ref "C46") (pin "1") (pinfunction "1_1") (pintype "passive"))
      (node (ref "C57") (pin "1") (pinfunction "1_1") (pintype "passive"))
      (node (ref "R28") (pin "P$1") (pinfunction "1_P$1") (pintype "passive"))
      (node (ref "U2") (pin "11") (pinfunction "AIN5_11") (pintype "bidirectional"))
    )
    (net (code "11") (name "/+IN2+") (class "Default")
      (node (ref "R28") (pin "P$2") (pinfunction "2_P$2") (pintype "passive"))
      (node (ref "X5") (pin "3") (pinfunction "3_3") (pintype "passive"))
      (node (ref "X6") (pin "3") (pinfunction "3_3") (pintype "passive"))
    )
    (net (code "12") (name "/+IN3") (class "Default")
      (node (ref "C38") (pin "1") (pinfunction "1_1") (pintype "passive"))
      (node (ref "C44") (pin "1") (pinfunction "1_1") (pintype "passive"))
      (node (ref "C55") (pin "1") (pinfunction "1_1") (pintype "passive"))
      (node (ref "R26") (pin "P$1") (pinfunction "1_P$1") (pintype "passive"))
      (node (ref "U2") (pin "9") (pinfunction "AIN3_9") (pintype "bidirectional"))
    )
    (net (code "13") (name "/+IN3+") (class "Default")
      (node (ref "R26") (pin "P$2") (pinfunction "2_P$2") (pintype "passive"))
      (node (ref "X5") (pin "5") (pinfunction "5_5") (pintype "passive"))
      (node (ref "X6") (pin "5") (pinfunction "5_5") (pintype "passive"))
    )
    (net (code "14") (name "/+IN4") (class "Default")
      (node (ref "C36") (pin "1") (pinfunction "1_1") (pintype "passive"))
      (node (ref "C42") (pin "1") (pinfunction "1_1") (pintype "passive"))
      (node (ref "C53") (pin "1") (pinfunction "1_1") (pintype "passive"))
      (node (ref "R24") (pin "P$1") (pinfunction "1_P$1") (pintype "passive"))
      (node (ref "U2") (pin "7") (pinfunction "AIN1_7") (pintype "bidirectional"))
    )
    (net (code "15") (name "/+IN4+") (class "Default")
      (node (ref "R24") (pin "P$2") (pinfunction "2_P$2") (pintype "passive"))
      (node (ref "X5") (pin "7") (pinfunction "7_7") (pintype "passive"))
      (node (ref "X6") (pin "7") (pinfunction "7_7") (pintype "passive"))
    )
    (net (code "16") (name "/+IN5") (class "Default")
      (node (ref "C86") (pin "1") (pinfunction "1_1") (pintype "passive"))
      (node (ref "C91") (pin "2") (pinfunction "2_2") (pintype "passive"))
      (node (ref "C94") (pin "2") (pinfunction "2_2") (pintype "passive"))
      (node (ref "R35") (pin "P$1") (pinfunction "1_P$1") (pintype "passive"))
      (node (ref "U5") (pin "13") (pinfunction "AIN7_13") (pintype "bidirectional"))
    )
    (net (code "17") (name "/+IN5+") (class "Default")
      (node (ref "R35") (pin "P$2") (pinfunction "2_P$2") (pintype "passive"))
      (node (ref "X6") (pin "9") (pinfunction "9_9") (pintype "passive"))
    )
    (net (code "18") (name "/+IN6") (class "Default")
      (node (ref "C84") (pin "1") (pinfunction "1_1") (pintype "passive"))
      (node (ref "C92") (pin "2") (pinfunction "2_2") (pintype "passive"))
      (node (ref "C95") (pin "2") (pinfunction "2_2") (pintype "passive"))
      (node (ref "R33") (pin "P$1") (pinfunction "1_P$1") (pintype "passive"))
      (node (ref "U5") (pin "11") (pinfunction "AIN5_11") (pintype "bidirectional"))
    )
    (net (code "19") (name "/+IN6+") (class "Default")
      (node (ref "R33") (pin "P$2") (pinfunction "2_P$2") (pintype "passive"))
      (node (ref "X6") (pin "11") (pinfunction "11_11") (pintype "passive"))
    )
    (net (code "20") (name "/+IN7") (class "Default")
      (node (ref "C81") (pin "1") (pinfunction "1_1") (pintype "passive"))
      (node (ref "C89") (pin "2") (pinfunction "2_2") (pintype "passive"))
      (node (ref "C96") (pin "2") (pinfunction "2_2") (pintype "passive"))
      (node (ref "R18") (pin "P$1") (pinfunction "1_P$1") (pintype "passive"))
      (node (ref "U5") (pin "9") (pinfunction "AIN3_9") (pintype "bidirectional"))
    )
    (net (code "21") (name "/+IN7+") (class "Default")
      (node (ref "R18") (pin "P$2") (pinfunction "2_P$2") (pintype "passive"))
      (node (ref "X6") (pin "13") (pinfunction "13_13") (pintype "passive"))
    )
    (net (code "22") (name "/+IN8") (class "Default")
      (node (ref "C87") (pin "1") (pinfunction "1_1") (pintype "passive"))
      (node (ref "C90") (pin "2") (pinfunction "2_2") (pintype "passive"))
      (node (ref "C93") (pin "2") (pinfunction "2_2") (pintype "passive"))
      (node (ref "R38") (pin "P$1") (pinfunction "1_P$1") (pintype "passive"))
      (node (ref "U5") (pin "7") (pinfunction "AIN1_7") (pintype "bidirectional"))
    )
    (net (code "23") (name "/+IN8+") (class "Default")
      (node (ref "R38") (pin "P$2") (pinfunction "2_P$2") (pintype "passive"))
      (node (ref "X6") (pin "15") (pinfunction "15_15") (pintype "passive"))
    )
    (net (code "24") (name "/-15V") (class "Default")
      (node (ref "C110") (pin "2") (pinfunction "2_2") (pintype "passive"))
      (node (ref "C27") (pin "MINUS") (pinfunction "-_MINUS") (pintype "passive"))
      (node (ref "C50") (pin "2") (pinfunction "2_2") (pintype "passive"))
      (node (ref "DC3") (pin "4") (pinfunction "-VOUT_4") (pintype "passive"))
      (node (ref "IC4") (pin "4") (pinfunction "-V_4") (pintype "power_in"))
    )
    (net (code "25") (name "/-IN1") (class "Default")
      (node (ref "C35") (pin "2") (pinfunction "2_2") (pintype "passive"))
      (node (ref "C41") (pin "2") (pinfunction "2_2") (pintype "passive"))
      (node (ref "C61") (pin "1") (pinfunction "1_1") (pintype "passive"))
      (node (ref "R21") (pin "P$1") (pinfunction "1_P$1") (pintype "passive"))
      (node (ref "U2") (pin "12") (pinfunction "AIN6_12") (pintype "bidirectional"))
    )
    (net (code "26") (name "/-IN1-") (class "Default")
      (node (ref "R21") (pin "P$2") (pinfunction "2_P$2") (pintype "passive"))
      (node (ref "X5") (pin "2") (pinfunction "2_2") (pintype "passive"))
      (node (ref "X6") (pin "2") (pinfunction "2_2") (pintype "passive"))
    )
    (net (code "27") (name "/-IN2") (class "Default")
      (node (ref "C40") (pin "2") (pinfunction "2_2") (pintype "passive"))
      (node (ref "C46") (pin "2") (pinfunction "2_2") (pintype "passive"))
      (node (ref "C56") (pin "1") (pinfunction "1_1") (pintype "passive"))
      (node (ref "R27") (pin "P$1") (pinfunction "1_P$1") (pintype "passive"))
      (node (ref "U2") (pin "10") (pinfunction "AIN4_10") (pintype "bidirectional"))
    )
    (net (code "28") (name "/-IN2-") (class "Default")
      (node (ref "R27") (pin "P$2") (pinfunction "2_P$2") (pintype "passive"))
      (node (ref "X5") (pin "4") (pinfunction "4_4") (pintype "passive"))
      (node (ref "X6") (pin "4") (pinfunction "4_4") (pintype "passive"))
    )
    (net (code "29") (name "/-IN3") (class "Default")
      (node (ref "C38") (pin "2") (pinfunction "2_2") (pintype "passive"))
      (node (ref "C44") (pin "2") (pinfunction "2_2") (pintype "passive"))
      (node (ref "C54") (pin "1") (pinfunction "1_1") (pintype "passive"))
      (node (ref "R25") (pin "P$1") (pinfunction "1_P$1") (pintype "passive"))
      (node (ref "U2") (pin "8") (pinfunction "AIN2_8") (pintype "bidirectional"))
    )
    (net (code "30") (name "/-IN3-") (class "Default")
      (node (ref "R25") (pin "P$2") (pinfunction "2_P$2") (pintype "passive"))
      (node (ref "X5") (pin "6") (pinfunction "6_6") (pintype "passive"))
      (node (ref "X6") (pin "6") (pinfunction "6_6") (pintype "passive"))
    )
    (net (code "31") (name "/-IN4") (class "Default")
      (node (ref "C36") (pin "2") (pinfunction "2_2") (pintype "passive"))
      (node (ref "C42") (pin "2") (pinfunction "2_2") (pintype "passive"))
      (node (ref "C52") (pin "1") (pinfunction "1_1") (pintype "passive"))
      (node (ref "R23") (pin "P$1") (pinfunction "1_P$1") (pintype "passive"))
      (node (ref "U2") (pin "6") (pinfunction "AIN0_6") (pintype "bidirectional"))
    )
    (net (code "32") (name "/-IN4-") (class "Default")
      (node (ref "R23") (pin "P$2") (pinfunction "2_P$2") (pintype "passive"))
      (node (ref "X5") (pin "8") (pinfunction "8_8") (pintype "passive"))
      (node (ref "X6") (pin "8") (pinfunction "8_8") (pintype "passive"))
    )
    (net (code "33") (name "/-IN5") (class "Default")
      (node (ref "C85") (pin "1") (pinfunction "1_1") (pintype "passive"))
      (node (ref "C91") (pin "1") (pinfunction "1_1") (pintype "passive"))
      (node (ref "C94") (pin "1") (pinfunction "1_1") (pintype "passive"))
      (node (ref "R34") (pin "P$1") (pinfunction "1_P$1") (pintype "passive"))
      (node (ref "U5") (pin "12") (pinfunction "AIN6_12") (pintype "bidirectional"))
    )
    (net (code "34") (name "/-IN5-") (class "Default")
      (node (ref "R34") (pin "P$2") (pinfunction "2_P$2") (pintype "passive"))
      (node (ref "X6") (pin "10") (pinfunction "10_10") (pintype "passive"))
    )
    (net (code "35") (name "/-IN6") (class "Default")
      (node (ref "C83") (pin "1") (pinfunction "1_1") (pintype "passive"))
      (node (ref "C92") (pin "1") (pinfunction "1_1") (pintype "passive"))
      (node (ref "C95") (pin "1") (pinfunction "1_1") (pintype "passive"))
      (node (ref "R36") (pin "P$1") (pinfunction "1_P$1") (pintype "passive"))
      (node (ref "U5") (pin "10") (pinfunction "AIN4_10") (pintype "bidirectional"))
    )
    (net (code "36") (name "/-IN6-") (class "Default")
      (node (ref "R36") (pin "P$2") (pinfunction "2_P$2") (pintype "passive"))
      (node (ref "X6") (pin "12") (pinfunction "12_12") (pintype "passive"))
    )
    (net (code "37") (name "/-IN7") (class "Default")
      (node (ref "C80") (pin "1") (pinfunction "1_1") (pintype "passive"))
      (node (ref "C89") (pin "1") (pinfunction "1_1") (pintype "passive"))
      (node (ref "C96") (pin "1") (pinfunction "1_1") (pintype "passive"))
      (node (ref "R37") (pin "P$1") (pinfunction "1_P$1") (pintype "passive"))
      (node (ref "U5") (pin "8") (pinfunction "AIN2_8") (pintype "bidirectional"))
    )
    (net (code "38") (name "/-IN7-") (class "Default")
      (node (ref "R37") (pin "P$2") (pinfunction "2_P$2") (pintype "passive"))
      (node (ref "X6") (pin "14") (pinfunction "14_14") (pintype "passive"))
    )
    (net (code "39") (name "/-IN8") (class "Default")
      (node (ref "C88") (pin "1") (pinfunction "1_1") (pintype "passive"))
      (node (ref "C90") (pin "1") (pinfunction "1_1") (pintype "passive"))
      (node (ref "C93") (pin "1") (pinfunction "1_1") (pintype "passive"))
      (node (ref "R39") (pin "P$1") (pinfunction "1_P$1") (pintype "passive"))
      (node (ref "U5") (pin "6") (pinfunction "AIN0_6") (pintype "bidirectional"))
    )
    (net (code "40") (name "/-IN8-") (class "Default")
      (node (ref "R39") (pin "P$2") (pinfunction "2_P$2") (pintype "passive"))
      (node (ref "X6") (pin "16") (pinfunction "16_16") (pintype "passive"))
    )
    (net (code "41") (name "/ADC2_CS") (class "Default")
      (node (ref "IC6") (pin "12") (pinfunction "VOC_12") (pintype "output"))
      (node (ref "RN2") (pin "1") (pinfunction "1_1") (pintype "passive"))
    )
    (net (code "42") (name "/ADC2_CS_") (class "Default")
      (node (ref "IC2") (pin "44") (pinfunction "IC3/INT3/RD10_44") (pintype "bidirectional"))
      (node (ref "IC6") (pin "5") (pinfunction "VIC_5") (pintype "input"))
      (node (ref "P6") (pin "P$1") (pinfunction "P$1_P$1") (pintype "bidirectional"))
    )
    (net (code "43") (name "/ADC2_DRDY") (class "Default")
      (node (ref "IC6") (pin "11") (pinfunction "VID_11") (pintype "input"))
      (node (ref "RN2") (pin "2") (pinfunction "1_2") (pintype "passive"))
    )
    (net (code "44") (name "/ADC2_DRDY_") (class "Default")
      (node (ref "IC2") (pin "43") (pinfunction "IC2/U1CTS/INT2/RD9_43") (pintype "bidirectional"))
      (node (ref "IC6") (pin "6") (pinfunction "VOD_6") (pintype "output"))
    )
    (net (code "45") (name "/ADC2_OSC1") (class "Default")
      (node (ref "C78") (pin "1") (pinfunction "1_1") (pintype "passive"))
      (node (ref "U5") (pin "19") (pinfunction "XTAL1_19") (pintype "bidirectional"))
      (node (ref "X7") (pin "1") (pinfunction "1_1") (pintype "passive"))
    )
    (net (code "46") (name "/ADC2_OSC2") (class "Default")
      (node (ref "C79") (pin "1") (pinfunction "1_1") (pintype "passive"))
      (node (ref "U5") (pin "18") (pinfunction "XTAL2_18") (pintype "bidirectional"))
      (node (ref "X7") (pin "2") (pinfunction "2_2") (pintype "passive"))
    )
    (net (code "47") (name "/ADC2_RESET") (class "Default")
      (node (ref "IC2") (pin "46") (pinfunction "OC1/RD0_46") (pintype "bidirectional"))
      (node (ref "IC6") (pin "3") (pinfunction "VIA_3") (pintype "input"))
    )
    (net (code "48") (name "/ADC2_RST") (class "Default")
      (node (ref "IC6") (pin "14") (pinfunction "VOA_14") (pintype "output"))
      (node (ref "U5") (pin "15") (pinfunction "~{RST}_15") (pintype "bidirectional"))
    )
    (net (code "49") (name "/ADC2_SYNC") (class "Default")
      (node (ref "IC6") (pin "13") (pinfunction "VOB_13") (pintype "output"))
      (node (ref "U5") (pin "14") (pinfunction "~{SYNC,}PDWN_14") (pintype "bidirectional"))
    )
    (net (code "50") (name "/ADC2_SYNC,PDOWN") (class "Default")
      (node (ref "IC2") (pin "45") (pinfunction "IC4/INT4/RD11_45") (pintype "bidirectional"))
      (node (ref "IC6") (pin "4") (pinfunction "VIB_4") (pintype "input"))
    )
    (net (code "51") (name "/ADC_DIN") (class "Default")
      (node (ref "IC1") (pin "4") (pinfunction "VIB_4") (pintype "input"))
      (node (ref "IC2") (pin "6") (pinfunction "SDO2/CN10/RG8_6") (pintype "bidirectional"))
      (node (ref "P2") (pin "P$1") (pinfunction "P$1_P$1") (pintype "bidirectional"))
    )
    (net (code "52") (name "/ADC_DOUT") (class "Default")
      (node (ref "IC1") (pin "6") (pinfunction "VOD_6") (pintype "output"))
      (node (ref "IC2") (pin "5") (pinfunction "SDI2/CN9/RG7_5") (pintype "bidirectional"))
      (node (ref "P3") (pin "P$1") (pinfunction "P$1_P$1") (pintype "bidirectional"))
    )
    (net (code "53") (name "/ADC_OSC1") (class "Default")
      (node (ref "C105") (pin "1") (pinfunction "1_1") (pintype "passive"))
      (node (ref "U2") (pin "19") (pinfunction "XTAL1_19") (pintype "bidirectional"))
      (node (ref "X4") (pin "1") (pinfunction "1_1") (pintype "passive"))
    )
    (net (code "54") (name "/ADC_OSC2") (class "Default")
      (node (ref "C106") (pin "1") (pinfunction "1_1") (pintype "passive"))
      (node (ref "U2") (pin "18") (pinfunction "XTAL2_18") (pintype "bidirectional"))
      (node (ref "X4") (pin "2") (pinfunction "2_2") (pintype "passive"))
    )
    (net (code "55") (name "/ADC_SCLK") (class "Default")
      (node (ref "IC1") (pin "3") (pinfunction "VIA_3") (pintype "input"))
      (node (ref "IC2") (pin "4") (pinfunction "SCK2/CN8/RG6_4") (pintype "bidirectional"))
      (node (ref "P4") (pin "P$1") (pinfunction "P$1_P$1") (pintype "bidirectional"))
    )
    (net (code "56") (name "/AVDD") (class "Default")
      (node (ref "IC2") (pin "19") (pinfunction "AVDD_19") (pintype "power_in"))
      (node (ref "R6") (pin "P$2") (pinfunction "2_P$2") (pintype "passive"))
    )
    (net (code "57") (name "/CN1") (class "Default")
      (node (ref "IC2") (pin "11") (pinfunction "AN5/IC8/CN7/RB5_11") (pintype "bidirectional"))
      (node (ref "R42") (pin "P$2") (pinfunction "2_P$2") (pintype "passive"))
      (node (ref "SV1") (pin "15") (pinfunction "15_15") (pintype "passive"))
    )
    (net (code "58") (name "/CN2") (class "Default")
      (node (ref "IC2") (pin "12") (pinfunction "AN4/IC7/CN6/RB4_12") (pintype "bidirectional"))
      (node (ref "R43") (pin "P$2") (pinfunction "2_P$2") (pintype "passive"))
      (node (ref "SV1") (pin "13") (pinfunction "13_13") (pintype "passive"))
    )
    (net (code "59") (name "/CN3") (class "Default")
      (node (ref "IC2") (pin "13") (pinfunction "AN3/CN5/RB3_13") (pintype "bidirectional"))
      (node (ref "R44") (pin "P$1") (pinfunction "1_P$1") (pintype "passive"))
      (node (ref "SV1") (pin "16") (pinfunction "16_16") (pintype "passive"))
    )
    (net (code "60") (name "/CN4") (class "Default")
      (node (ref "IC2") (pin "14") (pinfunction "AN2/SS1/CN4/RB2_14") (pintype "bidirectional"))
      (node (ref "R45") (pin "P$1") (pinfunction "1_P$1") (pintype "passive"))
      (node (ref "SV1") (pin "14") (pinfunction "14_14") (pintype "passive"))
    )
    (net (code "61") (name "/DIN") (class "Default")
      (node (ref "IC1") (pin "13") (pinfunction "VOB_13") (pintype "output"))
      (node (ref "RN1") (pin "4") (pinfunction "1_4") (pintype "passive"))
      (node (ref "RN2") (pin "4") (pinfunction "1_4") (pintype "passive"))
    )
    (net (code "62") (name "/DOUT") (class "Default")
      (node (ref "IC1") (pin "11") (pinfunction "VID_11") (pintype "input"))
      (node (ref "RN1") (pin "3") (pinfunction "1_3") (pintype "passive"))
      (node (ref "RN2") (pin "3") (pinfunction "1_3") (pintype "passive"))
    )
    (net (code "63") (name "/D_VDD(+5V)") (class "Default")
      (node (ref "C111") (pin "1") (pinfunction "1_1") (pintype "passive"))
      (node (ref "C23") (pin "2") (pinfunction "2_2") (pintype "passive"))
      (node (ref "C30") (pin "1") (pinfunction "1_1") (pintype "passive"))
      (node (ref "C43") (pin "1") (pinfunction "1_1") (pintype "passive"))
      (node (ref "C48") (pin "PLUS") (pinfunction "+_PLUS") (pintype "passive"))
      (node (ref "C59") (pin "1") (pinfunction "1_1") (pintype "passive"))
      (node (ref "DC2") (pin "6") (pinfunction "+VOUT_6") (pintype "passive"))
      (node (ref "IC3") (pin "1") (pinfunction "IN_1") (pintype "input"))
      (node (ref "IC5") (pin "7") (pinfunction "V+_7") (pintype "power_in"))
      (node (ref "U2") (pin "1") (pinfunction "AVDD_1") (pintype "bidirectional"))
      (node (ref "U5") (pin "1") (pinfunction "AVDD_1") (pintype "bidirectional"))
    )
    (net (code "64") (name "/EXT_START") (class "Default")
      (node (ref "IC2") (pin "29") (pinfunction "U2RTS/AN14/RB14_29") (pintype "bidirectional"))
      (node (ref "OK1") (pin "6") (pinfunction "VO_6") (pintype "passive"))
      (node (ref "R100") (pin "P$2") (pinfunction "2_P$2") (pintype "passive"))
    )
    (net (code "65") (name "/I_SENS") (class "Default")
      (node (ref "IC5") (pin "3") (pinfunction "+IN_3") (pintype "input"))
      (node (ref "R19") (pin "2") (pinfunction "2_2") (pintype "passive"))
      (node (ref "R20") (pin "2") (pinfunction "2_2") (pintype "passive"))
      (node (ref "R30") (pin "2") (pinfunction "2_2") (pintype "passive"))
      (node (ref "R32") (pin "2") (pinfunction "2_2") (pintype "passive"))
      (node (ref "X5") (pin "10") (pinfunction "10_10") (pintype "passive"))
      (node (ref "X6") (pin "18") (pinfunction "18_18") (pintype "passive"))
    )
    (net (code "66") (name "/LCD_DB4") (class "Default")
      (node (ref "IC2") (pin "61") (pinfunction "RG0_61") (pintype "bidirectional"))
      (node (ref "SV1") (pin "7") (pinfunction "7_7") (pintype "passive"))
    )
    (net (code "67") (name "/LCD_DB5") (class "Default")
      (node (ref "IC2") (pin "60") (pinfunction "RG1_60") (pintype "bidirectional"))
      (node (ref "SV1") (pin "8") (pinfunction "8_8") (pintype "passive"))
    )
    (net (code "68") (name "/LCD_DB6") (class "Default")
      (node (ref "IC2") (pin "15") (pinfunction "PGEC3/AN1/VREF-/CN3/RB1_15") (pintype "bidirectional"))
      (node (ref "SV1") (pin "9") (pinfunction "9_9") (pintype "passive"))
    )
    (net (code "69") (name "/LCD_DB7") (class "Default")
      (node (ref "IC2") (pin "16") (pinfunction "PGED3/AN0/VREF+/CN2/RB0_16") (pintype "bidirectional"))
      (node (ref "SV1") (pin "10") (pinfunction "10_10") (pintype "passive"))
    )
    (net (code "70") (name "/LCD_E") (class "Default")
      (node (ref "IC2") (pin "62") (pinfunction "RG14_62") (pintype "bidirectional"))
      (node (ref "SV1") (pin "6") (pinfunction "6_6") (pintype "passive"))
    )
    (net (code "71") (name "/LCD_RS") (class "Default")
      (node (ref "IC2") (pin "64") (pinfunction "RG13_64") (pintype "bidirectional"))
      (node (ref "SV1") (pin "4") (pinfunction "4_4") (pintype "passive"))
    )
    (net (code "72") (name "/LCD_RW") (class "Default")
      (node (ref "IC2") (pin "63") (pinfunction "RG12_63") (pintype "bidirectional"))
      (node (ref "SV1") (pin "5") (pinfunction "5_5") (pintype "passive"))
    )
    (net (code "73") (name "/MCU_RS485_RX1") (class "Default")
      (node (ref "SV3") (pin "13") (pinfunction "13_13") (pintype "passive"))
      (node (ref "U1") (pin "14") (pinfunction "A_14") (pintype "bidirectional"))
    )
    (net (code "74") (name "/MCU_RS485_RX2") (class "Default")
      (node (ref "SV3") (pin "14") (pinfunction "14_14") (pintype "passive"))
      (node (ref "U1") (pin "13") (pinfunction "B_13") (pintype "bidirectional"))
    )
    (net (code "75") (name "/MCU_RS485_TX1") (class "Default")
      (node (ref "SV3") (pin "17") (pinfunction "17_17") (pintype "passive"))
      (node (ref "U1") (pin "12") (pinfunction "Z_12") (pintype "bidirectional"))
    )
    (net (code "76") (name "/MCU_RS485_TX2") (class "Default")
      (node (ref "SV3") (pin "18") (pinfunction "18_18") (pintype "passive"))
      (node (ref "U1") (pin "11") (pinfunction "Y_11") (pintype "bidirectional"))
    )
    (net (code "77") (name "/OSC1") (class "Default")
      (node (ref "C11") (pin "1") (pinfunction "1_1") (pintype "passive"))
      (node (ref "IC2") (pin "39") (pinfunction "OSC1/CLKIN/RC12_39") (pintype "bidirectional"))
      (node (ref "R16") (pin "P$2") (pinfunction "2_P$2") (pintype "passive"))
      (node (ref "X2") (pin "1") (pinfunction "1_1") (pintype "passive"))
    )
    (net (code "78") (name "/OSC2") (class "Default")
      (node (ref "C12") (pin "1") (pinfunction "1_1") (pintype "passive"))
      (node (ref "IC2") (pin "40") (pinfunction "OSC2/CLKO/RC15_40") (pintype "bidirectional"))
      (node (ref "R16") (pin "P$1") (pinfunction "1_P$1") (pintype "passive"))
      (node (ref "X2") (pin "2") (pinfunction "2_2") (pintype "passive"))
    )
    (net (code "79") (name "/PGC") (class "Default")
      (node (ref "IC2") (pin "17") (pinfunction "PGEC1/AN6/OCFA/RB6_17") (pintype "bidirectional"))
      (node (ref "X1") (pin "P$5") (pinfunction "PGC_P$5") (pintype "bidirectional"))
    )
    (net (code "80") (name "/PGD") (class "Default")
      (node (ref "IC2") (pin "18") (pinfunction "PGED1/AN7/RB7_18") (pintype "bidirectional"))
      (node (ref "X1") (pin "P$4") (pinfunction "PGD_P$4") (pintype "bidirectional"))
    )
    (net (code "81") (name "/SCK2") (class "Default")
      (node (ref "IC2") (pin "35") (pinfunction "U1RTS/SCK1/INT0/RF6_35") (pintype "bidirectional"))
    )
    (net (code "82") (name "/SCLK") (class "Default")
      (node (ref "IC1") (pin "14") (pinfunction "VOA_14") (pintype "output"))
      (node (ref "R13") (pin "P$1") (pinfunction "1_P$1") (pintype "passive"))
      (node (ref "R17") (pin "P$1") (pinfunction "1_P$1") (pintype "passive"))
    )
    (net (code "83") (name "/SDI2,U1RX") (class "Default")
      (node (ref "IC2") (pin "34") (pinfunction "U1RX/SDI1/RF2_34") (pintype "bidirectional"))
      (node (ref "R40") (pin "P$2") (pinfunction "2_P$2") (pintype "passive"))
    )
    (net (code "84") (name "/SDO2,U1TX") (class "Default")
      (node (ref "IC2") (pin "33") (pinfunction "U1TX/SDO1/RF3_33") (pintype "bidirectional"))
      (node (ref "R41") (pin "P$2") (pinfunction "2_P$2") (pintype "passive"))
    )
    (net (code "85") (name "/VREF+") (class "Default")
      (node (ref "C33") (pin "1") (pinfunction "1_1") (pintype "passive"))
      (node (ref "C45") (pin "2") (pinfunction "2_2") (pintype "passive"))
      (node (ref "C62") (pin "2") (pinfunction "2_2") (pintype "passive"))
      (node (ref "IC4") (pin "3") (pinfunction "+_3") (pintype "input"))
      (node (ref "U2") (pin "4") (pinfunction "VREFP_4") (pintype "bidirectional"))
      (node (ref "U5") (pin "4") (pinfunction "VREFP_4") (pintype "bidirectional"))
      (node (ref "U7") (pin "6") (pinfunction "VOUT_6") (pintype "bidirectional"))
      (node (ref "X5") (pin "14") (pinfunction "14_14") (pintype "passive"))
      (node (ref "X6") (pin "22") (pinfunction "22_22") (pintype "passive"))
    )
    (net (code "86") (name "/XPORT_RX") (class "Default")
      (node (ref "IC2") (pin "32") (pinfunction "U2TX/SCL2/CN18/RF5_32") (pintype "bidirectional"))
      (node (ref "XP1") (pin "5") (pinfunction "IN_5") (pintype "input"))
    )
    (net (code "87") (name "/XPORT_TX") (class "Default")
      (node (ref "IC2") (pin "31") (pinfunction "U2RX/SDA2/CN17/RF4_31") (pintype "bidirectional"))
      (node (ref "XP1") (pin "4") (pinfunction "OUT_4") (pintype "output"))
    )
    (net (code "88") (name "/~{ADC_CS}") (class "Default")
      (node (ref "IC1") (pin "5") (pinfunction "VIC_5") (pintype "input"))
      (node (ref "IC2") (pin "8") (pinfunction "SS2/CN11/RG9_8") (pintype "bidirectional"))
      (node (ref "P1") (pin "P$1") (pinfunction "P$1_P$1") (pintype "bidirectional"))
    )
    (net (code "89") (name "/~{ADC_DRDY}") (class "Default")
      (node (ref "IC2") (pin "49") (pinfunction "OC2/RD1_49") (pintype "bidirectional"))
      (node (ref "IC7") (pin "5") (pinfunction "VOC_5") (pintype "tri_state"))
      (node (ref "P5") (pin "P$1") (pinfunction "P$1_P$1") (pintype "bidirectional"))
    )
    (net (code "90") (name "/~{ADC_RST}") (class "Default")
      (node (ref "IC2") (pin "51") (pinfunction "OC4/RD3_51") (pintype "bidirectional"))
      (node (ref "IC7") (pin "3") (pinfunction "VIA_3") (pintype "input"))
    )
    (net (code "91") (name "/~{ADC_SYNC}") (class "Default")
      (node (ref "IC2") (pin "50") (pinfunction "OC3/RD2_50") (pintype "bidirectional"))
      (node (ref "IC7") (pin "4") (pinfunction "VIB_4") (pintype "input"))
    )
    (net (code "92") (name "/~{CS}") (class "Default")
      (node (ref "IC1") (pin "12") (pinfunction "VOC_12") (pintype "output"))
      (node (ref "RN1") (pin "1") (pinfunction "1_1") (pintype "passive"))
    )
    (net (code "93") (name "/~{DRDY}") (class "Default")
      (node (ref "IC7") (pin "12") (pinfunction "VIC_12") (pintype "input"))
      (node (ref "RN1") (pin "2") (pinfunction "1_2") (pintype "passive"))
    )
    (net (code "94") (name "/~{MCLR_}") (class "Default")
      (node (ref "IC2") (pin "7") (pinfunction "~{MCLR}_7") (pintype "bidirectional"))
      (node (ref "JP1") (pin "P$2") (pinfunction "P$2_P$2") (pintype "bidirectional"))
      (node (ref "R8") (pin "P$2") (pinfunction "2_P$2") (pintype "passive"))
    )
    (net (code "95") (name "/~{MCLR}") (class "Default")
      (node (ref "JP1") (pin "P$1") (pinfunction "P$1_P$1") (pintype "bidirectional"))
      (node (ref "X1") (pin "P$1") (pinfunction "MCLR_P$1") (pintype "bidirectional"))
    )
    (net (code "96") (name "/~{RST}") (class "Default")
      (node (ref "IC7") (pin "14") (pinfunction "VOA_14") (pintype "tri_state"))
      (node (ref "U2") (pin "15") (pinfunction "~{RST}_15") (pintype "bidirectional"))
    )
    (net (code "97") (name "/~{SYNC,PDWN}") (class "Default")
      (node (ref "IC7") (pin "13") (pinfunction "VOB_13") (pintype "tri_state"))
      (node (ref "U2") (pin "14") (pinfunction "~{SYNC,}PDWN_14") (pintype "bidirectional"))
    )
    (net (code "98") (name "/~{XPORT_RST}") (class "Default")
      (node (ref "IC2") (pin "30") (pinfunction "AN15/OCFB/CN12/RB15_30") (pintype "bidirectional"))
      (node (ref "R7") (pin "P$2") (pinfunction "2_P$2") (pintype "passive"))
      (node (ref "XP1") (pin "3") (pinfunction "~{RESET}_3") (pintype "input"))
    )
    (net (code "99") (name "0V") (class "Default")
      (node (ref "C1") (pin "2") (pinfunction "2_2") (pintype "passive"))
      (node (ref "C10") (pin "2") (pinfunction "2_2") (pintype "passive"))
      (node (ref "C100") (pin "2") (pinfunction "2_2") (pintype "passive"))
      (node (ref "C101") (pin "2") (pinfunction "2_2") (pintype "passive"))
      (node (ref "C102") (pin "2") (pinfunction "2_2") (pintype "passive"))
      (node (ref "C103") (pin "2") (pinfunction "2_2") (pintype "passive"))
      (node (ref "C104") (pin "1") (pinfunction "1_1") (pintype "passive"))
      (node (ref "C107") (pin "2") (pinfunction "2_2") (pintype "passive"))
      (node (ref "C108") (pin "2") (pinfunction "2_2") (pintype "passive"))
      (node (ref "C109") (pin "2") (pinfunction "2_2") (pintype "passive"))
      (node (ref "C11") (pin "2") (pinfunction "2_2") (pintype "passive"))
      (node (ref "C12") (pin "2") (pinfunction "2_2") (pintype "passive"))
      (node (ref "C13") (pin "1") (pinfunction "1_1") (pintype "passive"))
      (node (ref "C15") (pin "2") (pinfunction "2_2") (pintype "passive"))
      (node (ref "C17") (pin "2") (pinfunction "2_2") (pintype "passive"))
      (node (ref "C18") (pin "2") (pinfunction "2_2") (pintype "passive"))
      (node (ref "C19") (pin "1") (pinfunction "1_1") (pintype "passive"))
      (node (ref "C2") (pin "2") (pinfunction "2_2") (pintype "passive"))
      (node (ref "C20") (pin "MINUS") (pinfunction "-_MINUS") (pintype "passive"))
      (node (ref "C25") (pin "1") (pinfunction "1_1") (pintype "passive"))
      (node (ref "C26") (pin "2") (pinfunction "2_2") (pintype "passive"))
      (node (ref "C29") (pin "1") (pinfunction "1_1") (pintype "passive"))
      (node (ref "C3") (pin "1") (pinfunction "1_1") (pintype "passive"))
      (node (ref "C31") (pin "2") (pinfunction "2_2") (pintype "passive"))
      (node (ref "C32") (pin "MINUS") (pinfunction "-_MINUS") (pintype "passive"))
      (node (ref "C4") (pin "2") (pinfunction "2_2") (pintype "passive"))
      (node (ref "C49") (pin "2") (pinfunction "2_2") (pintype "passive"))
      (node (ref "C5") (pin "MINUS") (pinfunction "-_MINUS") (pintype "passive"))
      (node (ref "C6") (pin "1") (pinfunction "1_1") (pintype "passive"))
      (node (ref "C60") (pin "2") (pinfunction "2_2") (pintype "passive"))
      (node (ref "C63") (pin "1") (pinfunction "1_1") (pintype "passive"))
      (node (ref "C64") (pin "2") (pinfunction "2_2") (pintype "passive"))
      (node (ref "C65") (pin "2") (pinfunction "2_2") (pintype "passive"))
      (node (ref "C68") (pin "2") (pinfunction "2_2") (pintype "passive"))
      (node (ref "C69") (pin "2") (pinfunction "2_2") (pintype "passive"))
      (node (ref "C7") (pin "2") (pinfunction "2_2") (pintype "passive"))
      (node (ref "C70") (pin "2") (pinfunction "2_2") (pintype "passive"))
      (node (ref "C74") (pin "2") (pinfunction "2_2") (pintype "passive"))
      (node (ref "C8") (pin "2") (pinfunction "2_2") (pintype "passive"))
      (node (ref "C9") (pin "MINUS") (pinfunction "-_MINUS") (pintype "passive"))
      (node (ref "D1") (pin "3") (pinfunction "GND_3") (pintype "power_in"))
      (node (ref "D3") (pin "A") (pinfunction "A_A") (pintype "passive"))
      (node (ref "DA1") (pin "2") (pinfunction "GND_2") (pintype "bidirectional"))
      (node (ref "DA1") (pin "21") (pinfunction "GND1_21") (pintype "bidirectional"))
      (node (ref "DA2") (pin "2") (pinfunction "GND_2") (pintype "bidirectional"))
      (node (ref "DA2") (pin "21") (pinfunction "GND1_21") (pintype "bidirectional"))
      (node (ref "DC1") (pin "2") (pinfunction "-VIN_2") (pintype "passive"))
      (node (ref "DC1") (pin "5") (pinfunction "COM_5") (pintype "passive"))
      (node (ref "DC2") (pin "2") (pinfunction "-VIN_2") (pintype "passive"))
      (node (ref "DC3") (pin "2") (pinfunction "-VIN_2") (pintype "passive"))
      (node (ref "HL2") (pin "K") (pinfunction "C_K") (pintype "passive"))
      (node (ref "HL6") (pin "K") (pinfunction "C_K") (pintype "passive"))
      (node (ref "IC1") (pin "2") (pinfunction "GND1_2") (pintype "power_in"))
      (node (ref "IC1") (pin "8") (pinfunction "GND1_8") (pintype "power_in"))
      (node (ref "IC2") (pin "20") (pinfunction "AVSS_20") (pintype "power_in"))
      (node (ref "IC2") (pin "25") (pinfunction "VSS_25") (pintype "power_in"))
      (node (ref "IC2") (pin "41") (pinfunction "VSS_41") (pintype "power_in"))
      (node (ref "IC2") (pin "9") (pinfunction "VSS_9") (pintype "power_in"))
      (node (ref "IC6") (pin "2") (pinfunction "GND1_2") (pintype "power_in"))
      (node (ref "IC6") (pin "8") (pinfunction "GND1_8") (pintype "power_in"))
      (node (ref "IC7") (pin "2") (pinfunction "GND1_2") (pintype "input"))
      (node (ref "IC7") (pin "8") (pinfunction "GND1_8") (pintype "input"))
      (node (ref "OK1") (pin "5") (pinfunction "GND_5") (pintype "passive"))
      (node (ref "POT1") (pin "1") (pinfunction "1_1") (pintype "passive"))
      (node (ref "R11") (pin "P$1") (pinfunction "1_P$1") (pintype "passive"))
      (node (ref "R42") (pin "P$1") (pinfunction "1_P$1") (pintype "passive"))
      (node (ref "R43") (pin "P$1") (pinfunction "1_P$1") (pintype "passive"))
      (node (ref "R44") (pin "P$2") (pinfunction "2_P$2") (pintype "passive"))
      (node (ref "R45") (pin "P$2") (pinfunction "2_P$2") (pintype "passive"))
      (node (ref "SV1") (pin "1") (pinfunction "1_1") (pintype "passive"))
      (node (ref "SV1") (pin "12") (pinfunction "12_12") (pintype "passive"))
      (node (ref "SV3") (pin "10") (pinfunction "10_10") (pintype "passive"))
      (node (ref "SV3") (pin "5") (pinfunction "5_5") (pintype "passive"))
      (node (ref "SV3") (pin "6") (pinfunction "6_6") (pintype "passive"))
      (node (ref "SV3") (pin "7") (pinfunction "7_7") (pintype "passive"))
      (node (ref "SV3") (pin "8") (pinfunction "8_8") (pintype "passive"))
      (node (ref "SV3") (pin "9") (pinfunction "9_9") (pintype "passive"))
      (node (ref "U1") (pin "2") (pinfunction "GND1.1_2") (pintype "bidirectional"))
      (node (ref "U1") (pin "4") (pinfunction "~{RE}_4") (pintype "bidirectional"))
      (node (ref "U1") (pin "7") (pinfunction "GND1.2_7") (pintype "bidirectional"))
      (node (ref "U1") (pin "8") (pinfunction "GND1.3_8") (pintype "bidirectional"))
      (node (ref "U4") (pin "1") (pinfunction "1_1") (pintype "bidirectional"))
      (node (ref "X1") (pin "P$3") (pinfunction "GND_P$3") (pintype "bidirectional"))
      (node (ref "X5") (pin "G1") (pinfunction "G1_G1") (pintype "passive"))
      (node (ref "X5") (pin "G2") (pinfunction "G2_G2") (pintype "passive"))
      (node (ref "X6") (pin "G1") (pinfunction "G1_G1") (pintype "passive"))
      (node (ref "X6") (pin "G2") (pinfunction "G2_G2") (pintype "passive"))
      (node (ref "XP1") (pin "1") (pinfunction "GND_1") (pintype "power_in"))
      (node (ref "XP1") (pin "SH1") (pinfunction "SH_SH1") (pintype "passive"))
      (node (ref "XP1") (pin "SH2") (pinfunction "SH_SH2") (pintype "passive"))
    )
    (net (code "100") (name "DGND") (class "Default")
      (node (ref "C105") (pin "2") (pinfunction "2_2") (pintype "passive"))
      (node (ref "C106") (pin "2") (pinfunction "2_2") (pintype "passive"))
      (node (ref "C110") (pin "1") (pinfunction "1_1") (pintype "passive"))
      (node (ref "C111") (pin "2") (pinfunction "2_2") (pintype "passive"))
      (node (ref "C21") (pin "1") (pinfunction "1_1") (pintype "passive"))
      (node (ref "C22") (pin "1") (pinfunction "1_1") (pintype "passive"))
      (node (ref "C23") (pin "1") (pinfunction "1_1") (pintype "passive"))
      (node (ref "C24") (pin "2") (pinfunction "2_2") (pintype "passive"))
      (node (ref "C27") (pin "PLUS") (pinfunction "+_PLUS") (pintype "passive"))
      (node (ref "C28") (pin "1") (pinfunction "1_1") (pintype "passive"))
      (node (ref "C30") (pin "2") (pinfunction "2_2") (pintype "passive"))
      (node (ref "C33") (pin "2") (pinfunction "2_2") (pintype "passive"))
      (node (ref "C34") (pin "MINUS") (pinfunction "-_MINUS") (pintype "passive"))
      (node (ref "C37") (pin "1") (pinfunction "1_1") (pintype "passive"))
      (node (ref "C39") (pin "2") (pinfunction "2_2") (pintype "passive"))
      (node (ref "C43") (pin "2") (pinfunction "2_2") (pintype "passive"))
      (node (ref "C45") (pin "1") (pinfunction "1_1") (pintype "passive"))
      (node (ref "C47") (pin "2") (pinfunction "2_2") (pintype "passive"))
      (node (ref "C48") (pin "MINUS") (pinfunction "-_MINUS") (pintype "passive"))
      (node (ref "C50") (pin "1") (pinfunction "1_1") (pintype "passive"))
      (node (ref "C51") (pin "2") (pinfunction "2_2") (pintype "passive"))
      (node (ref "C52") (pin "2") (pinfunction "2_2") (pintype "passive"))
      (node (ref "C53") (pin "2") (pinfunction "2_2") (pintype "passive"))
      (node (ref "C54") (pin "2") (pinfunction "2_2") (pintype "passive"))
      (node (ref "C55") (pin "2") (pinfunction "2_2") (pintype "passive"))
      (node (ref "C56") (pin "2") (pinfunction "2_2") (pintype "passive"))
      (node (ref "C57") (pin "2") (pinfunction "2_2") (pintype "passive"))
      (node (ref "C58") (pin "1") (pinfunction "1_1") (pintype "passive"))
      (node (ref "C59") (pin "2") (pinfunction "2_2") (pintype "passive"))
      (node (ref "C61") (pin "2") (pinfunction "2_2") (pintype "passive"))
      (node (ref "C62") (pin "1") (pinfunction "1_1") (pintype "passive"))
      (node (ref "C66") (pin "1") (pinfunction "1_1") (pintype "passive"))
      (node (ref "C67") (pin "1") (pinfunction "1_1") (pintype "passive"))
      (node (ref "C71") (pin "1") (pinfunction "1_1") (pintype "passive"))
      (node (ref "C72") (pin "1") (pinfunction "1_1") (pintype "passive"))
      (node (ref "C73") (pin "1") (pinfunction "1_1") (pintype "passive"))
      (node (ref "C75") (pin "1") (pinfunction "1_1") (pintype "passive"))
      (node (ref "C76") (pin "1") (pinfunction "1_1") (pintype "passive"))
      (node (ref "C77") (pin "1") (pinfunction "1_1") (pintype "passive"))
      (node (ref "C78") (pin "2") (pinfunction "2_2") (pintype "passive"))
      (node (ref "C79") (pin "2") (pinfunction "2_2") (pintype "passive"))
      (node (ref "C80") (pin "2") (pinfunction "2_2") (pintype "passive"))
      (node (ref "C81") (pin "2") (pinfunction "2_2") (pintype "passive"))
      (node (ref "C82") (pin "2") (pinfunction "2_2") (pintype "passive"))
      (node (ref "C83") (pin "2") (pinfunction "2_2") (pintype "passive"))
      (node (ref "C84") (pin "2") (pinfunction "2_2") (pintype "passive"))
      (node (ref "C85") (pin "2") (pinfunction "2_2") (pintype "passive"))
      (node (ref "C86") (pin "2") (pinfunction "2_2") (pintype "passive"))
      (node (ref "C87") (pin "2") (pinfunction "2_2") (pintype "passive"))
      (node (ref "C88") (pin "2") (pinfunction "2_2") (pintype "passive"))
      (node (ref "DC2") (pin "5") (pinfunction "COM_5") (pintype "passive"))
      (node (ref "DC3") (pin "5") (pinfunction "COM_5") (pintype "passive"))
      (node (ref "IC1") (pin "15") (pinfunction "GND2_15") (pintype "power_in"))
      (node (ref "IC1") (pin "9") (pinfunction "GND2_9") (pintype "power_in"))
      (node (ref "IC3") (pin "2") (pinfunction "GND_2") (pintype "power_in"))
      (node (ref "IC3") (pin "4") (pinfunction "GND_4") (pintype "power_in"))
      (node (ref "IC4") (pin "2") (pinfunction "-_2") (pintype "input"))
      (node (ref "IC5") (pin "4") (pinfunction "V-_4") (pintype "power_in"))
      (node (ref "IC6") (pin "15") (pinfunction "GND2_15") (pintype "power_in"))
      (node (ref "IC6") (pin "9") (pinfunction "GND2_9") (pintype "power_in"))
      (node (ref "IC7") (pin "15") (pinfunction "GND2_15") (pintype "input"))
      (node (ref "IC7") (pin "9") (pinfunction "GND2_9") (pintype "input"))
      (node (ref "R11") (pin "P$2") (pinfunction "2_P$2") (pintype "passive"))
      (node (ref "R12") (pin "P$1") (pinfunction "1_P$1") (pintype "passive"))
      (node (ref "U2") (pin "17") (pinfunction "DGND_17") (pintype "bidirectional"))
      (node (ref "U2") (pin "2") (pinfunction "AGND_2") (pintype "bidirectional"))
      (node (ref "U2") (pin "3") (pinfunction "VREFN_3") (pintype "bidirectional"))
      (node (ref "U2") (pin "5") (pinfunction "AINCOM_5") (pintype "bidirectional"))
      (node (ref "U5") (pin "17") (pinfunction "DGND_17") (pintype "bidirectional"))
      (node (ref "U5") (pin "2") (pinfunction "AGND_2") (pintype "bidirectional"))
      (node (ref "U5") (pin "3") (pinfunction "VREFN_3") (pintype "bidirectional"))
      (node (ref "U5") (pin "5") (pinfunction "AINCOM_5") (pintype "bidirectional"))
      (node (ref "U7") (pin "4") (pinfunction "GND_4") (pintype "bidirectional"))
      (node (ref "X5") (pin "11") (pinfunction "11_11") (pintype "passive"))
      (node (ref "X5") (pin "12") (pinfunction "12_12") (pintype "passive"))
      (node (ref "X5") (pin "13") (pinfunction "13_13") (pintype "passive"))
      (node (ref "X5") (pin "15") (pinfunction "15_15") (pintype "passive"))
      (node (ref "X5") (pin "9") (pinfunction "9_9") (pintype "passive"))
      (node (ref "X6") (pin "17") (pinfunction "17_17") (pintype "passive"))
      (node (ref "X6") (pin "19") (pinfunction "19_19") (pintype "passive"))
      (node (ref "X6") (pin "20") (pinfunction "20_20") (pintype "passive"))
      (node (ref "X6") (pin "21") (pinfunction "21_21") (pintype "passive"))
      (node (ref "X6") (pin "23") (pinfunction "23_23") (pintype "passive"))
      (node (ref "X6") (pin "24") (pinfunction "24_24") (pintype "passive"))
      (node (ref "X6") (pin "25") (pinfunction "25_25") (pintype "passive"))
    )
    (net (code "101") (name "Net-(C20-+)") (class "Default")
      (node (ref "C107") (pin "1") (pinfunction "1_1") (pintype "passive"))
      (node (ref "C108") (pin "1") (pinfunction "1_1") (pintype "passive"))
      (node (ref "C19") (pin "2") (pinfunction "2_2") (pintype "passive"))
      (node (ref "C20") (pin "PLUS") (pinfunction "+_PLUS") (pintype "passive"))
      (node (ref "C29") (pin "2") (pinfunction "2_2") (pintype "passive"))
      (node (ref "C32") (pin "PLUS") (pinfunction "+_PLUS") (pintype "passive"))
      (node (ref "DA2") (pin "4") (pinfunction "VOUT_4") (pintype "bidirectional"))
      (node (ref "DC2") (pin "1") (pinfunction "+VIN_1") (pintype "passive"))
      (node (ref "DC3") (pin "1") (pinfunction "+VIN_1") (pintype "passive"))
    )
    (net (code "102") (name "Net-(D1-RST)") (class "Default")
      (node (ref "D1") (pin "1") (pinfunction "RST_1") (pintype "output"))
      (node (ref "JP1") (pin "P$3") (pinfunction "P$3_P$3") (pintype "bidirectional"))
    )
    (net (code "103") (name "Net-(DA1-NBP)") (class "Default")
      (node (ref "C3") (pin "2") (pinfunction "2_2") (pintype "passive"))
      (node (ref "DA1") (pin "3") (pinfunction "NBP_3") (pintype "bidirectional"))
    )
    (net (code "104") (name "Net-(DA2-NBP)") (class "Default")
      (node (ref "C25") (pin "2") (pinfunction "2_2") (pintype "passive"))
      (node (ref "DA2") (pin "3") (pinfunction "NBP_3") (pintype "bidirectional"))
    )
    (net (code "105") (name "Net-(F1-Pad1)") (class "Default")
      (node (ref "F1") (pin "1") (pinfunction "1_1") (pintype "passive"))
      (node (ref "SV3") (pin "1") (pinfunction "1_1") (pintype "passive"))
      (node (ref "SV3") (pin "2") (pinfunction "2_2") (pintype "passive"))
      (node (ref "SV3") (pin "3") (pinfunction "3_3") (pintype "passive"))
      (node (ref "SV3") (pin "4") (pinfunction "4_4") (pintype "passive"))
    )
    (net (code "106") (name "Net-(IC2-CAP{slash}VDDCORE)") (class "Default")
      (node (ref "C101") (pin "1") (pinfunction "1_1") (pintype "passive"))
      (node (ref "IC2") (pin "56") (pinfunction "CAP/VDDCORE_56") (pintype "power_in"))
    )
    (net (code "107") (name "Net-(IC2-TDI{slash}AN13{slash}RB13)") (class "Default")
      (node (ref "IC2") (pin "28") (pinfunction "TDI/AN13/RB13_28") (pintype "input"))
      (node (ref "R5") (pin "P$1") (pinfunction "1_P$1") (pintype "passive"))
    )
    (net (code "108") (name "Net-(IC4-OUT)") (class "Default")
      (node (ref "IC4") (pin "6") (pinfunction "OUT_6") (pintype "output"))
      (node (ref "JP3") (pin "P$2") (pinfunction "P$2_P$2") (pintype "bidirectional"))
    )
    (net (code "109") (name "Net-(IC4-REF)") (class "Default")
      (node (ref "IC4") (pin "5") (pinfunction "REF_5") (pintype "passive"))
      (node (ref "IC5") (pin "2") (pinfunction "-IN_2") (pintype "input"))
      (node (ref "IC5") (pin "6") (pinfunction "OUT_6") (pintype "output"))
    )
    (net (code "110") (name "Net-(JP3-PadP$1)") (class "Default")
      (node (ref "JP3") (pin "P$1") (pinfunction "P$1_P$1") (pintype "bidirectional"))
      (node (ref "R14") (pin "2") (pinfunction "2_2") (pintype "passive"))
    )
    (net (code "111") (name "Net-(JP3-PadP$3)") (class "Default")
      (node (ref "JP3") (pin "P$3") (pinfunction "P$3_P$3") (pintype "bidirectional"))
      (node (ref "R29") (pin "1") (pinfunction "1_1") (pintype "passive"))
      (node (ref "R31") (pin "1") (pinfunction "1_1") (pintype "passive"))
    )
    (net (code "112") (name "Net-(OK1-A)") (class "Default")
      (node (ref "OK1") (pin "2") (pinfunction "A_2") (pintype "passive"))
      (node (ref "R104") (pin "P$2") (pinfunction "2_P$2") (pintype "passive"))
    )
    (net (code "113") (name "Net-(OK1-C)") (class "Default")
      (node (ref "JP2") (pin "1") (pinfunction "1_1") (pintype "passive"))
      (node (ref "OK1") (pin "3") (pinfunction "C_3") (pintype "passive"))
    )
    (net (code "114") (name "Net-(POT1-Pad3)") (class "Default")
      (node (ref "POT1") (pin "3") (pinfunction "3_3") (pintype "passive"))
      (node (ref "SV1") (pin "3") (pinfunction "3_3") (pintype "passive"))
    )
    (net (code "115") (name "Net-(R5-2)") (class "Default")
      (node (ref "HL2") (pin "A") (pinfunction "A_A") (pintype "passive"))
      (node (ref "R5") (pin "P$2") (pinfunction "2_P$2") (pintype "passive"))
    )
    (net (code "116") (name "Net-(R9-Pad1)") (class "Default")
      (node (ref "R9") (pin "1") (pinfunction "1_1") (pintype "passive"))
      (node (ref "SV1") (pin "11") (pinfunction "11_11") (pintype "passive"))
    )
    (net (code "117") (name "Net-(R10-2)") (class "Default")
      (node (ref "HL6") (pin "A") (pinfunction "A_A") (pintype "passive"))
      (node (ref "R10") (pin "P$2") (pinfunction "2_P$2") (pintype "passive"))
    )
    (net (code "118") (name "Net-(R13-2)") (class "Default")
      (node (ref "R13") (pin "P$2") (pinfunction "2_P$2") (pintype "passive"))
      (node (ref "U2") (pin "24") (pinfunction "SCLK_24") (pintype "bidirectional"))
    )
    (net (code "119") (name "Net-(R14-Pad1)") (class "Default")
      (node (ref "R14") (pin "1") (pinfunction "1_1") (pintype "passive"))
      (node (ref "R15") (pin "1") (pinfunction "1_1") (pintype "passive"))
    )
    (net (code "120") (name "Net-(R15-Pad2)") (class "Default")
      (node (ref "R15") (pin "2") (pinfunction "2_2") (pintype "passive"))
      (node (ref "R19") (pin "1") (pinfunction "1_1") (pintype "passive"))
      (node (ref "R20") (pin "1") (pinfunction "1_1") (pintype "passive"))
    )
    (net (code "121") (name "Net-(R17-2)") (class "Default")
      (node (ref "R17") (pin "P$2") (pinfunction "2_P$2") (pintype "passive"))
      (node (ref "U5") (pin "24") (pinfunction "SCLK_24") (pintype "bidirectional"))
    )
    (net (code "122") (name "Net-(R29-Pad2)") (class "Default")
      (node (ref "R29") (pin "2") (pinfunction "2_2") (pintype "passive"))
      (node (ref "R30") (pin "1") (pinfunction "1_1") (pintype "passive"))
    )
    (net (code "123") (name "Net-(R31-Pad2)") (class "Default")
      (node (ref "R31") (pin "2") (pinfunction "2_2") (pintype "passive"))
      (node (ref "R32") (pin "1") (pinfunction "1_1") (pintype "passive"))
    )
    (net (code "124") (name "Net-(R40-1)") (class "Default")
      (node (ref "C104") (pin "2") (pinfunction "2_2") (pintype "passive"))
      (node (ref "R40") (pin "P$1") (pinfunction "1_P$1") (pintype "passive"))
      (node (ref "U1") (pin "3") (pinfunction "R_3") (pintype "bidirectional"))
    )
    (net (code "125") (name "Net-(R41-1)") (class "Default")
      (node (ref "C109") (pin "1") (pinfunction "1_1") (pintype "passive"))
      (node (ref "R41") (pin "P$1") (pinfunction "1_P$1") (pintype "passive"))
      (node (ref "U1") (pin "6") (pinfunction "D_6") (pintype "bidirectional"))
    )
    (net (code "126") (name "Net-(R104-1)") (class "Default")
      (node (ref "JP2") (pin "2") (pinfunction "2_2") (pintype "passive"))
      (node (ref "R104") (pin "P$1") (pinfunction "1_P$1") (pintype "passive"))
    )
    (net (code "127") (name "Net-(RN1A-2)") (class "Default")
      (node (ref "RN1") (pin "8") (pinfunction "2_8") (pintype "passive"))
      (node (ref "U2") (pin "20") (pinfunction "~{CS}_20") (pintype "bidirectional"))
    )
    (net (code "128") (name "Net-(RN1B-2)") (class "Default")
      (node (ref "RN1") (pin "7") (pinfunction "2_7") (pintype "passive"))
      (node (ref "U2") (pin "21") (pinfunction "~{DRDY}_21") (pintype "bidirectional"))
    )
    (net (code "129") (name "Net-(RN1C-2)") (class "Default")
      (node (ref "RN1") (pin "6") (pinfunction "2_6") (pintype "passive"))
      (node (ref "U2") (pin "22") (pinfunction "DOUT_22") (pintype "bidirectional"))
    )
    (net (code "130") (name "Net-(RN1D-2)") (class "Default")
      (node (ref "RN1") (pin "5") (pinfunction "2_5") (pintype "passive"))
      (node (ref "U2") (pin "23") (pinfunction "DIN_23") (pintype "bidirectional"))
    )
    (net (code "131") (name "Net-(RN2A-2)") (class "Default")
      (node (ref "RN2") (pin "8") (pinfunction "2_8") (pintype "passive"))
      (node (ref "U5") (pin "20") (pinfunction "~{CS}_20") (pintype "bidirectional"))
    )
    (net (code "132") (name "Net-(RN2B-2)") (class "Default")
      (node (ref "RN2") (pin "7") (pinfunction "2_7") (pintype "passive"))
      (node (ref "U5") (pin "21") (pinfunction "~{DRDY}_21") (pintype "bidirectional"))
    )
    (net (code "133") (name "Net-(RN2C-2)") (class "Default")
      (node (ref "RN2") (pin "6") (pinfunction "2_6") (pintype "passive"))
      (node (ref "U5") (pin "22") (pinfunction "DOUT_22") (pintype "bidirectional"))
    )
    (net (code "134") (name "Net-(RN2D-2)") (class "Default")
      (node (ref "RN2") (pin "5") (pinfunction "2_5") (pintype "passive"))
      (node (ref "U5") (pin "23") (pinfunction "DIN_23") (pintype "bidirectional"))
    )
    (net (code "135") (name "PE") (class "Default")
      (node (ref "C14") (pin "MINUS") (pinfunction "-_MINUS") (pintype "passive"))
      (node (ref "C16") (pin "2") (pinfunction "2_2") (pintype "passive"))
      (node (ref "C97") (pin "1") (pinfunction "1_1") (pintype "passive"))
      (node (ref "C98") (pin "1") (pinfunction "1_1") (pintype "passive"))
      (node (ref "C99") (pin "2") (pinfunction "2_2") (pintype "passive"))
      (node (ref "DC1") (pin "4") (pinfunction "-VOUT_4") (pintype "passive"))
      (node (ref "IC8") (pin "2") (pinfunction "GND_2") (pintype "power_in"))
      (node (ref "IC8") (pin "4") (pinfunction "GND_4") (pintype "power_in"))
      (node (ref "SV3") (pin "11") (pinfunction "11_11") (pintype "passive"))
      (node (ref "SV3") (pin "12") (pinfunction "12_12") (pintype "passive"))
      (node (ref "SV3") (pin "15") (pinfunction "15_15") (pintype "passive"))
      (node (ref "SV3") (pin "16") (pinfunction "16_16") (pintype "passive"))
      (node (ref "SV3") (pin "19") (pinfunction "19_19") (pintype "passive"))
      (node (ref "SV3") (pin "20") (pinfunction "20_20") (pintype "passive"))
      (node (ref "U1") (pin "10") (pinfunction "GND2.2_10") (pintype "bidirectional"))
      (node (ref "U1") (pin "15") (pinfunction "GND2.3_15") (pintype "bidirectional"))
      (node (ref "U1") (pin "9") (pinfunction "GND2.1_9") (pintype "bidirectional"))
    )
    (net (code "136") (name "unconnected-(DC2--VOUT-Pad4)") (class "Default")
      (node (ref "DC2") (pin "4") (pinfunction "-VOUT_4") (pintype "passive"))
    )
    (net (code "137") (name "unconnected-(IC2-AN9{slash}RB9-Pad22)") (class "Default")
      (node (ref "IC2") (pin "22") (pinfunction "AN9/RB9_22") (pintype "bidirectional"))
    )
    (net (code "138") (name "unconnected-(IC2-AN16{slash}T2CK{slash}T7CK{slash}RC1-Pad2)") (class "Default")
      (node (ref "IC2") (pin "2") (pinfunction "AN16/T2CK/T7CK/RC1_2") (pintype "bidirectional"))
    )
    (net (code "139") (name "unconnected-(IC2-AN17{slash}T3CK{slash}T6CK{slash}RC2-Pad3)") (class "Default")
      (node (ref "IC2") (pin "3") (pinfunction "AN17/T3CK/T6CK/RC2_3") (pintype "bidirectional"))
    )
    (net (code "140") (name "unconnected-(IC2-C1RX{slash}RF0-Pad58)") (class "Default")
      (node (ref "IC2") (pin "58") (pinfunction "C1RX/RF0_58") (pintype "bidirectional"))
    )
    (net (code "141") (name "unconnected-(IC2-C1TX{slash}RF1-Pad59)") (class "Default")
      (node (ref "IC2") (pin "59") (pinfunction "C1TX/RF1_59") (pintype "bidirectional"))
    )
    (net (code "142") (name "unconnected-(IC2-IC1{slash}INT1{slash}RD8-Pad42)") (class "Default")
      (node (ref "IC2") (pin "42") (pinfunction "IC1/INT1/RD8_42") (pintype "bidirectional"))
    )
    (net (code "143") (name "unconnected-(IC2-OC5{slash}IC5{slash}CN13{slash}RD4-Pad52)") (class "Default")
      (node (ref "IC2") (pin "52") (pinfunction "OC5/IC5/CN13/RD4_52") (pintype "bidirectional"))
    )
    (net (code "144") (name "unconnected-(IC2-OC6{slash}IC6{slash}CN14{slash}RD5-Pad53)") (class "Default")
      (node (ref "IC2") (pin "53") (pinfunction "OC6/IC6/CN14/RD5_53") (pintype "bidirectional"))
    )
    (net (code "145") (name "unconnected-(IC2-OC7{slash}CN15{slash}RD6-Pad54)") (class "Default")
      (node (ref "IC2") (pin "54") (pinfunction "OC7/CN15/RD6_54") (pintype "bidirectional"))
    )
    (net (code "146") (name "unconnected-(IC2-OC8{slash}CN16{slash}RD7-Pad55)") (class "Default")
      (node (ref "IC2") (pin "55") (pinfunction "OC8/CN16/RD7_55") (pintype "bidirectional"))
    )
    (net (code "147") (name "unconnected-(IC2-PGEC2{slash}SOSCO{slash}T1CK{slash}CN0{slash}RC14-Pad48)") (class "Default")
      (node (ref "IC2") (pin "48") (pinfunction "PGEC2/SOSCO/T1CK/CN0/RC14_48") (pintype "bidirectional"))
    )
    (net (code "148") (name "unconnected-(IC2-PGED2{slash}SOSCI{slash}T4CK{slash}CN1{slash}RC13-Pad47)") (class "Default")
      (node (ref "IC2") (pin "47") (pinfunction "PGED2/SOSCI/T4CK/CN1/RC13_47") (pintype "bidirectional"))
    )
    (net (code "149") (name "unconnected-(IC2-RG15-Pad1)") (class "Default")
      (node (ref "IC2") (pin "1") (pinfunction "RG15_1") (pintype "bidirectional"))
    )
    (net (code "150") (name "unconnected-(IC2-SCL1{slash}RG2-Pad37)") (class "Default")
      (node (ref "IC2") (pin "37") (pinfunction "SCL1/RG2_37") (pintype "bidirectional"))
    )
    (net (code "151") (name "unconnected-(IC2-SDA1{slash}RG3-Pad36)") (class "Default")
      (node (ref "IC2") (pin "36") (pinfunction "SDA1/RG3_36") (pintype "bidirectional"))
    )
    (net (code "152") (name "unconnected-(IC2-TCK{slash}AN12{slash}RB12-Pad27)") (class "Default")
      (node (ref "IC2") (pin "27") (pinfunction "TCK/AN12/RB12_27") (pintype "input"))
    )
    (net (code "153") (name "unconnected-(IC2-TDO{slash}AN11{slash}RB11-Pad24)") (class "Default")
      (node (ref "IC2") (pin "24") (pinfunction "TDO/AN11/RB11_24") (pintype "output"))
    )
    (net (code "154") (name "unconnected-(IC2-TMS{slash}AN10{slash}RB10-Pad23)") (class "Default")
      (node (ref "IC2") (pin "23") (pinfunction "TMS/AN10/RB10_23") (pintype "input"))
    )
    (net (code "155") (name "unconnected-(IC2-U2CTS{slash}AN8{slash}RB8-Pad21)") (class "Default")
      (node (ref "IC2") (pin "21") (pinfunction "U2CTS/AN8/RB8_21") (pintype "bidirectional"))
    )
    (net (code "156") (name "unconnected-(IC4-RG-Pad1)") (class "Default")
      (node (ref "IC4") (pin "1") (pinfunction "RG_1") (pintype "passive"))
    )
    (net (code "157") (name "unconnected-(IC4-RG-Pad8)") (class "Default")
      (node (ref "IC4") (pin "8") (pinfunction "RG_8") (pintype "passive"))
    )
    (net (code "158") (name "unconnected-(IC7-NC-Pad6)") (class "Default")
      (node (ref "IC7") (pin "6") (pinfunction "NC_6") (pintype "no_connect"))
    )
    (net (code "159") (name "unconnected-(IC7-NC-Pad11)") (class "Default")
      (node (ref "IC7") (pin "11") (pinfunction "NC_11") (pintype "no_connect"))
    )
    (net (code "160") (name "unconnected-(U2-D0{slash}CLKOUT-Pad25)") (class "Default")
      (node (ref "U2") (pin "25") (pinfunction "D0/CLKOUT_25") (pintype "bidirectional"))
    )
    (net (code "161") (name "unconnected-(U2-D1-Pad26)") (class "Default")
      (node (ref "U2") (pin "26") (pinfunction "D1_26") (pintype "bidirectional"))
    )
    (net (code "162") (name "unconnected-(U2-D2-Pad27)") (class "Default")
      (node (ref "U2") (pin "27") (pinfunction "D2_27") (pintype "bidirectional"))
    )
    (net (code "163") (name "unconnected-(U2-D3-Pad28)") (class "Default")
      (node (ref "U2") (pin "28") (pinfunction "D3_28") (pintype "bidirectional"))
    )
    (net (code "164") (name "unconnected-(U5-D0{slash}CLKOUT-Pad25)") (class "Default")
      (node (ref "U5") (pin "25") (pinfunction "D0/CLKOUT_25") (pintype "bidirectional"))
    )
    (net (code "165") (name "unconnected-(U5-D1-Pad26)") (class "Default")
      (node (ref "U5") (pin "26") (pinfunction "D1_26") (pintype "bidirectional"))
    )
    (net (code "166") (name "unconnected-(U5-D2-Pad27)") (class "Default")
      (node (ref "U5") (pin "27") (pinfunction "D2_27") (pintype "bidirectional"))
    )
    (net (code "167") (name "unconnected-(U5-D3-Pad28)") (class "Default")
      (node (ref "U5") (pin "28") (pinfunction "D3_28") (pintype "bidirectional"))
    )
    (net (code "168") (name "unconnected-(U7-DNC1-Pad1)") (class "Default")
      (node (ref "U7") (pin "1") (pinfunction "DNC1_1") (pintype "bidirectional"))
    )
    (net (code "169") (name "unconnected-(U7-DNC2-Pad8)") (class "Default")
      (node (ref "U7") (pin "8") (pinfunction "DNC2_8") (pintype "bidirectional"))
    )
    (net (code "170") (name "unconnected-(U7-NC-Pad7)") (class "Default")
      (node (ref "U7") (pin "7") (pinfunction "NC_7") (pintype "bidirectional"))
    )
    (net (code "171") (name "unconnected-(U7-TEMP-Pad3)") (class "Default")
      (node (ref "U7") (pin "3") (pinfunction "TEMP_3") (pintype "bidirectional"))
    )
    (net (code "172") (name "unconnected-(U7-TRIM-Pad5)") (class "Default")
      (node (ref "U7") (pin "5") (pinfunction "TRIM_5") (pintype "bidirectional"))
    )
    (net (code "173") (name "unconnected-(XP1-CP1{slash}RTS{slash}CTS-Pad6)") (class "Default")
      (node (ref "XP1") (pin "6") (pinfunction "CP1/RTS/CTS_6") (pintype "bidirectional"))
    )
    (net (code "174") (name "unconnected-(XP1-CP2{slash}DTR{slash}DCD-Pad7)") (class "Default")
      (node (ref "XP1") (pin "7") (pinfunction "CP2/DTR/DCD_7") (pintype "bidirectional"))
    )
    (net (code "175") (name "unconnected-(XP1-CP3{slash}CTS{slash}DCD-Pad8)") (class "Default")
      (node (ref "XP1") (pin "8") (pinfunction "CP3/CTS/DCD_8") (pintype "bidirectional"))
    )
  )
)
